# unified.net
KiCad netlist of a schematic drawn in EAGLE
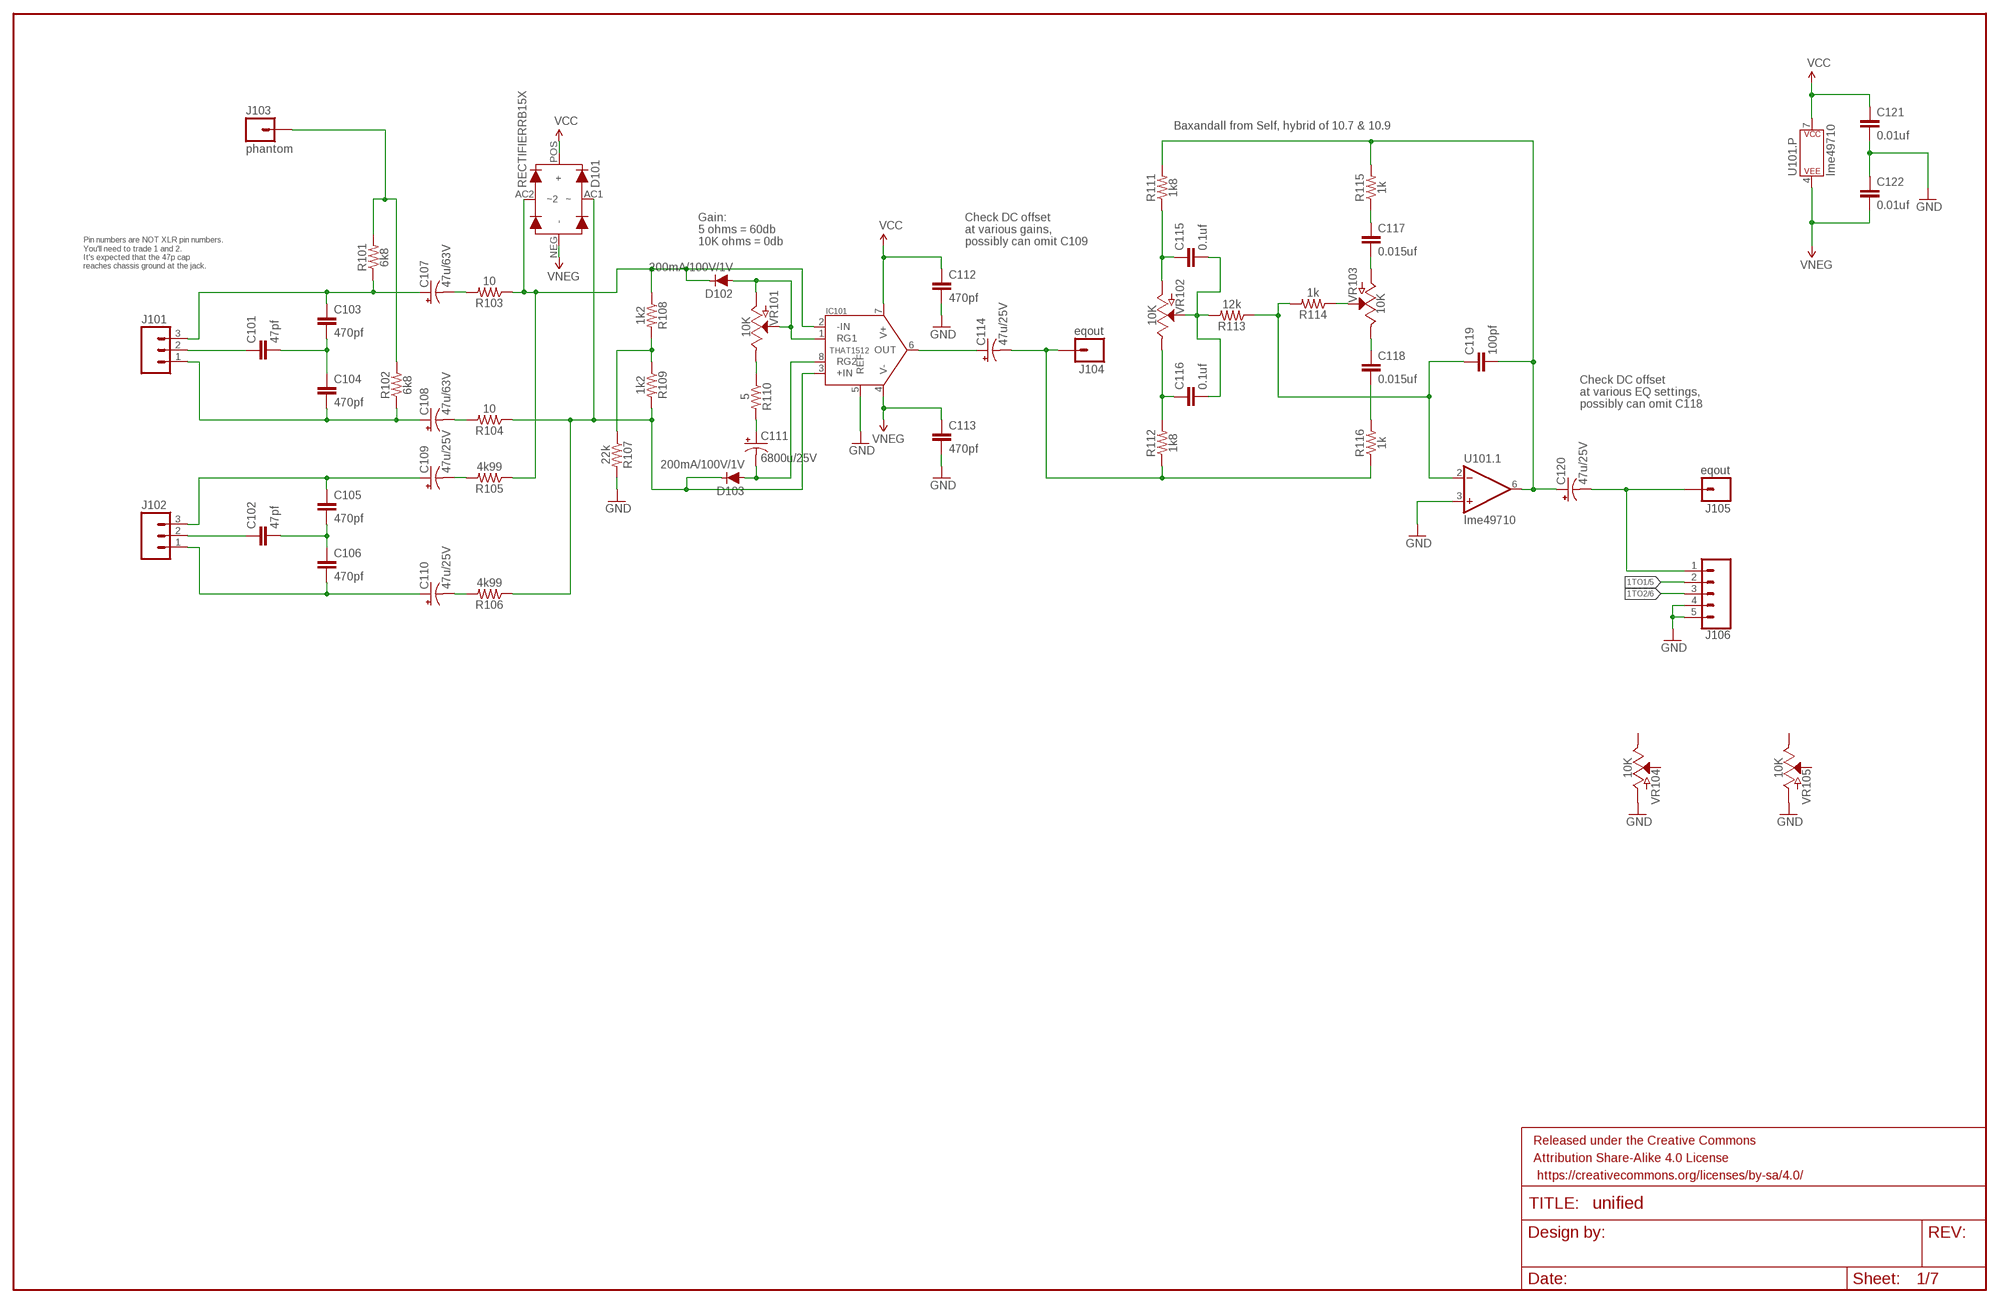
[diagram p0: schematic, sheet 1]
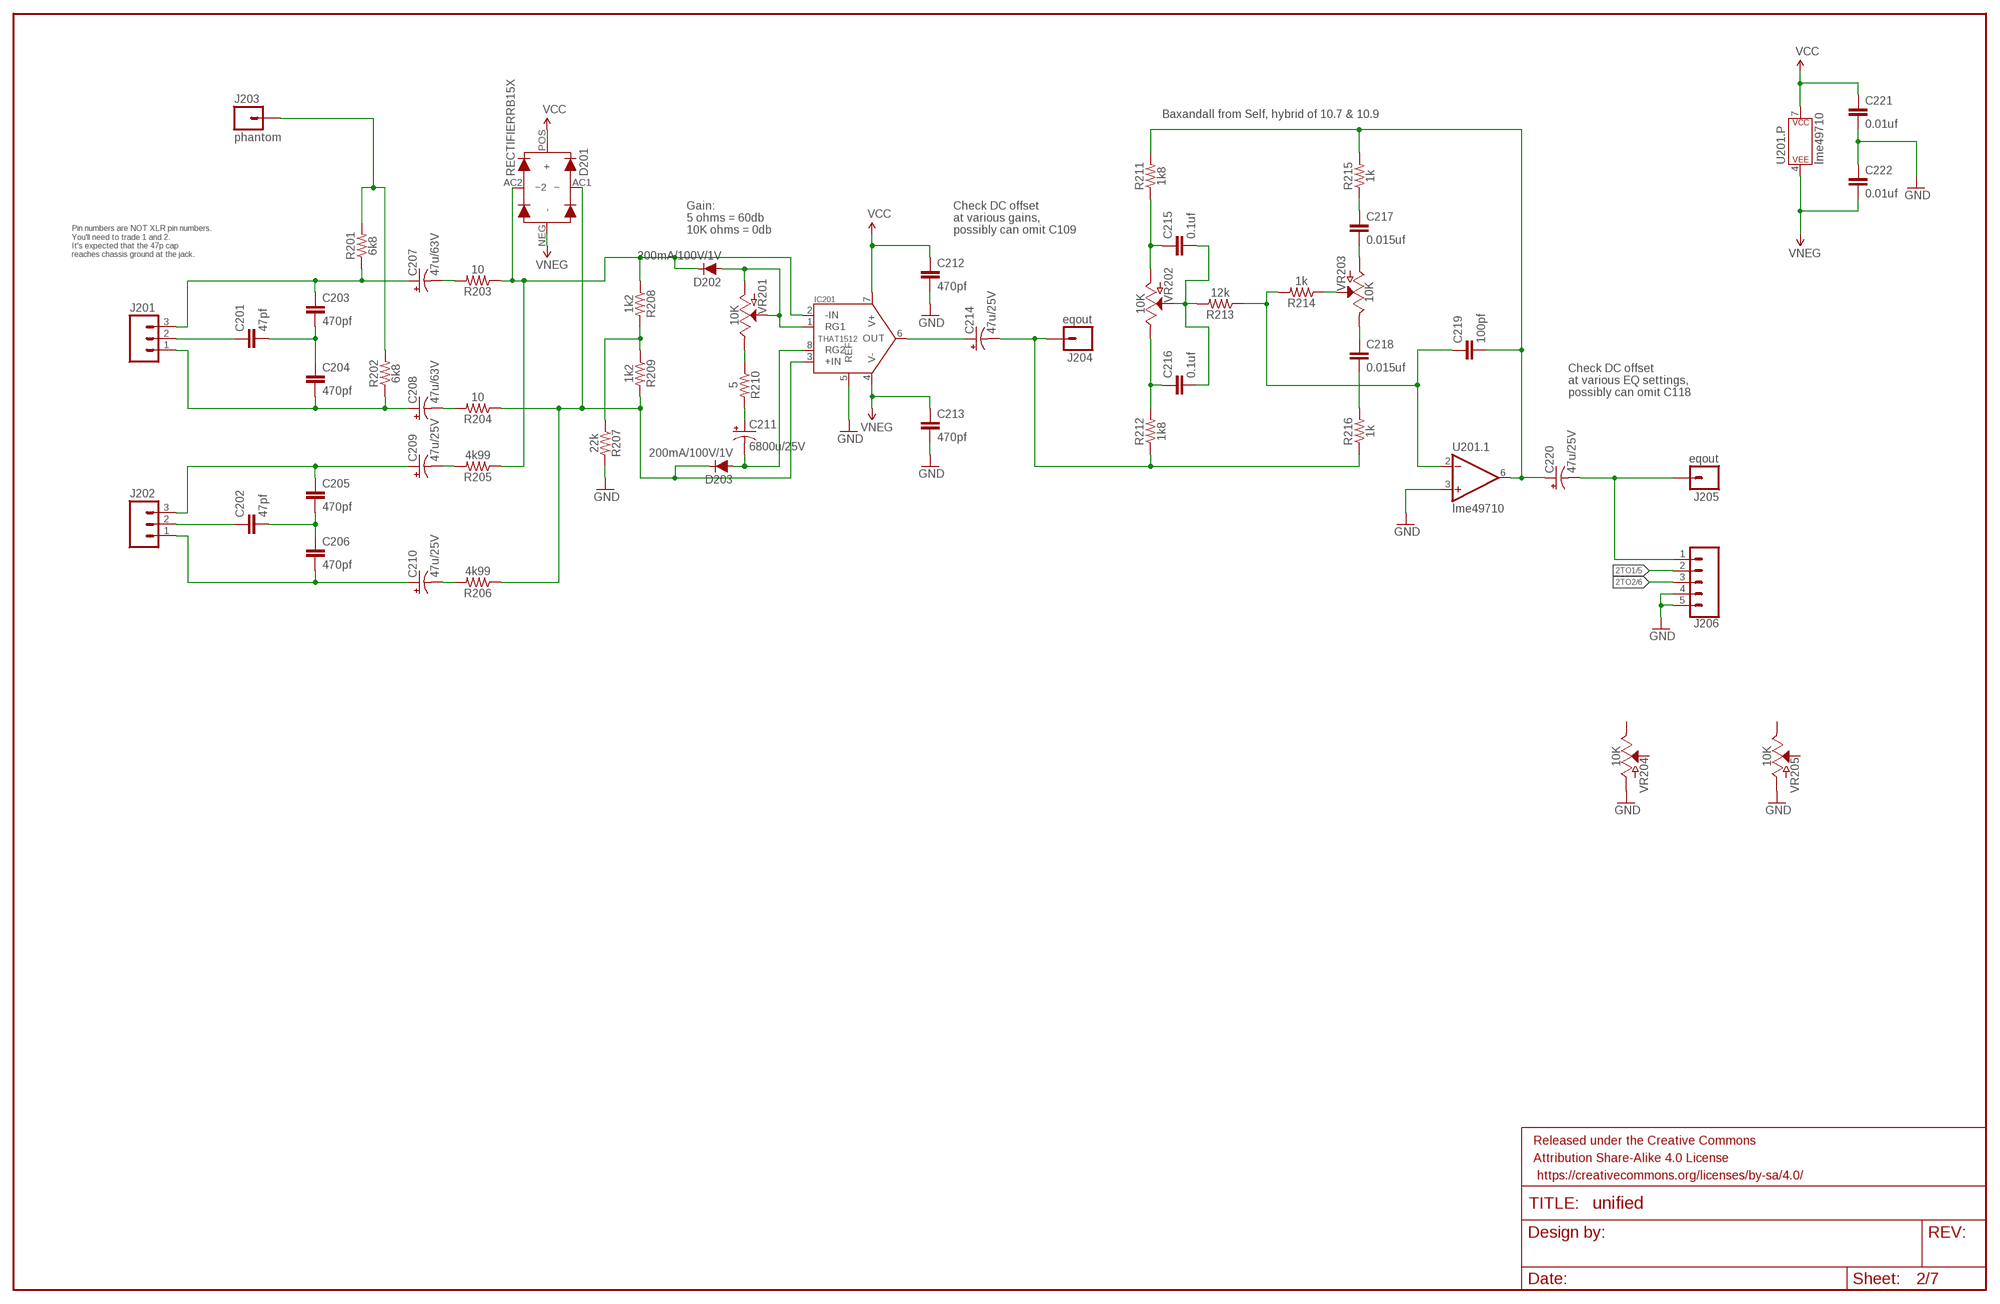
[diagram p1: schematic, sheet 2]
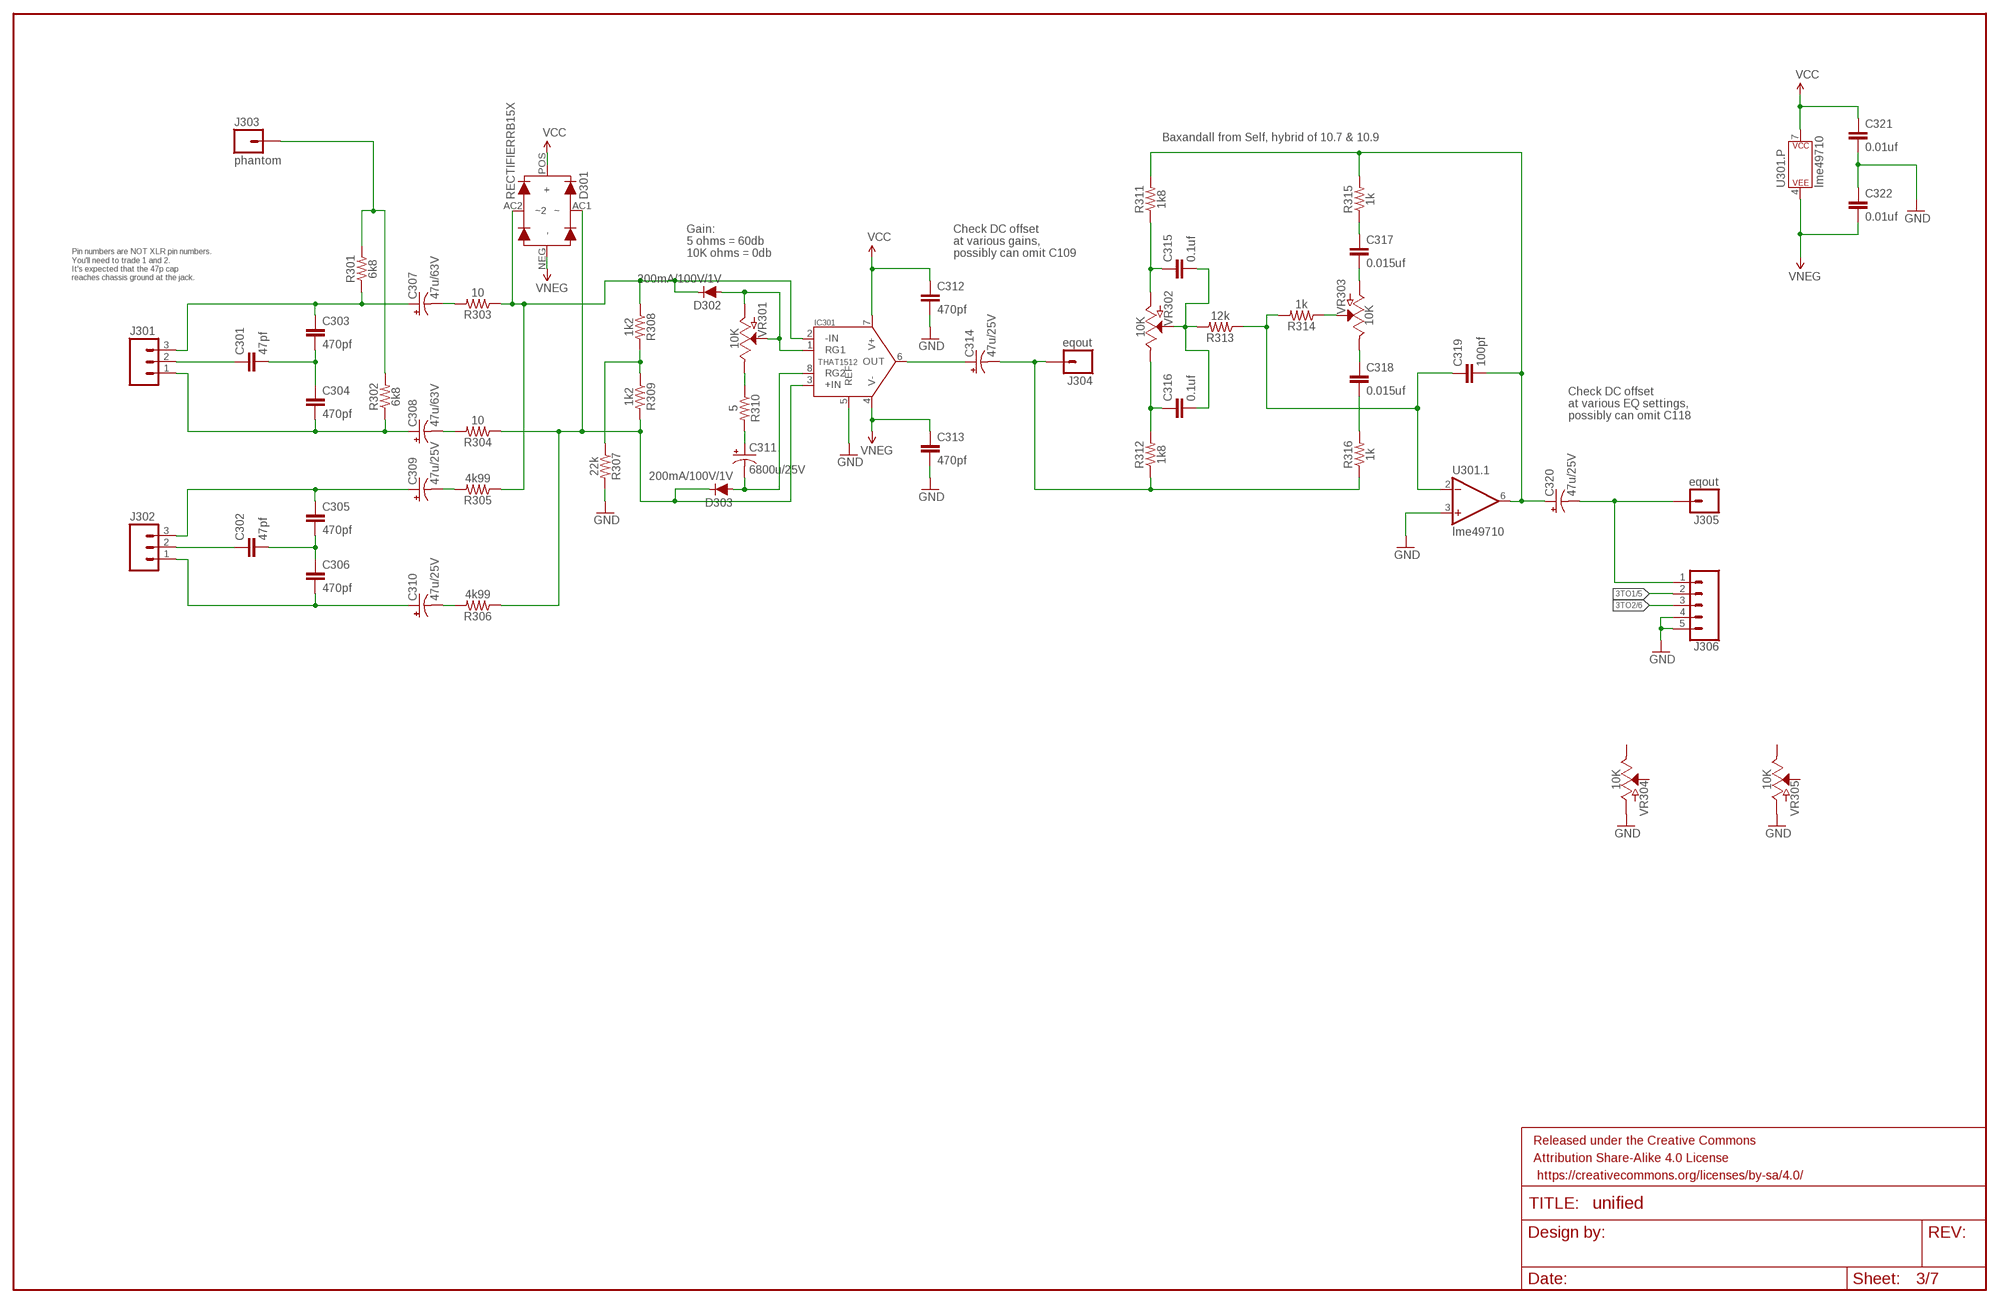
[diagram p2: schematic, sheet 3]
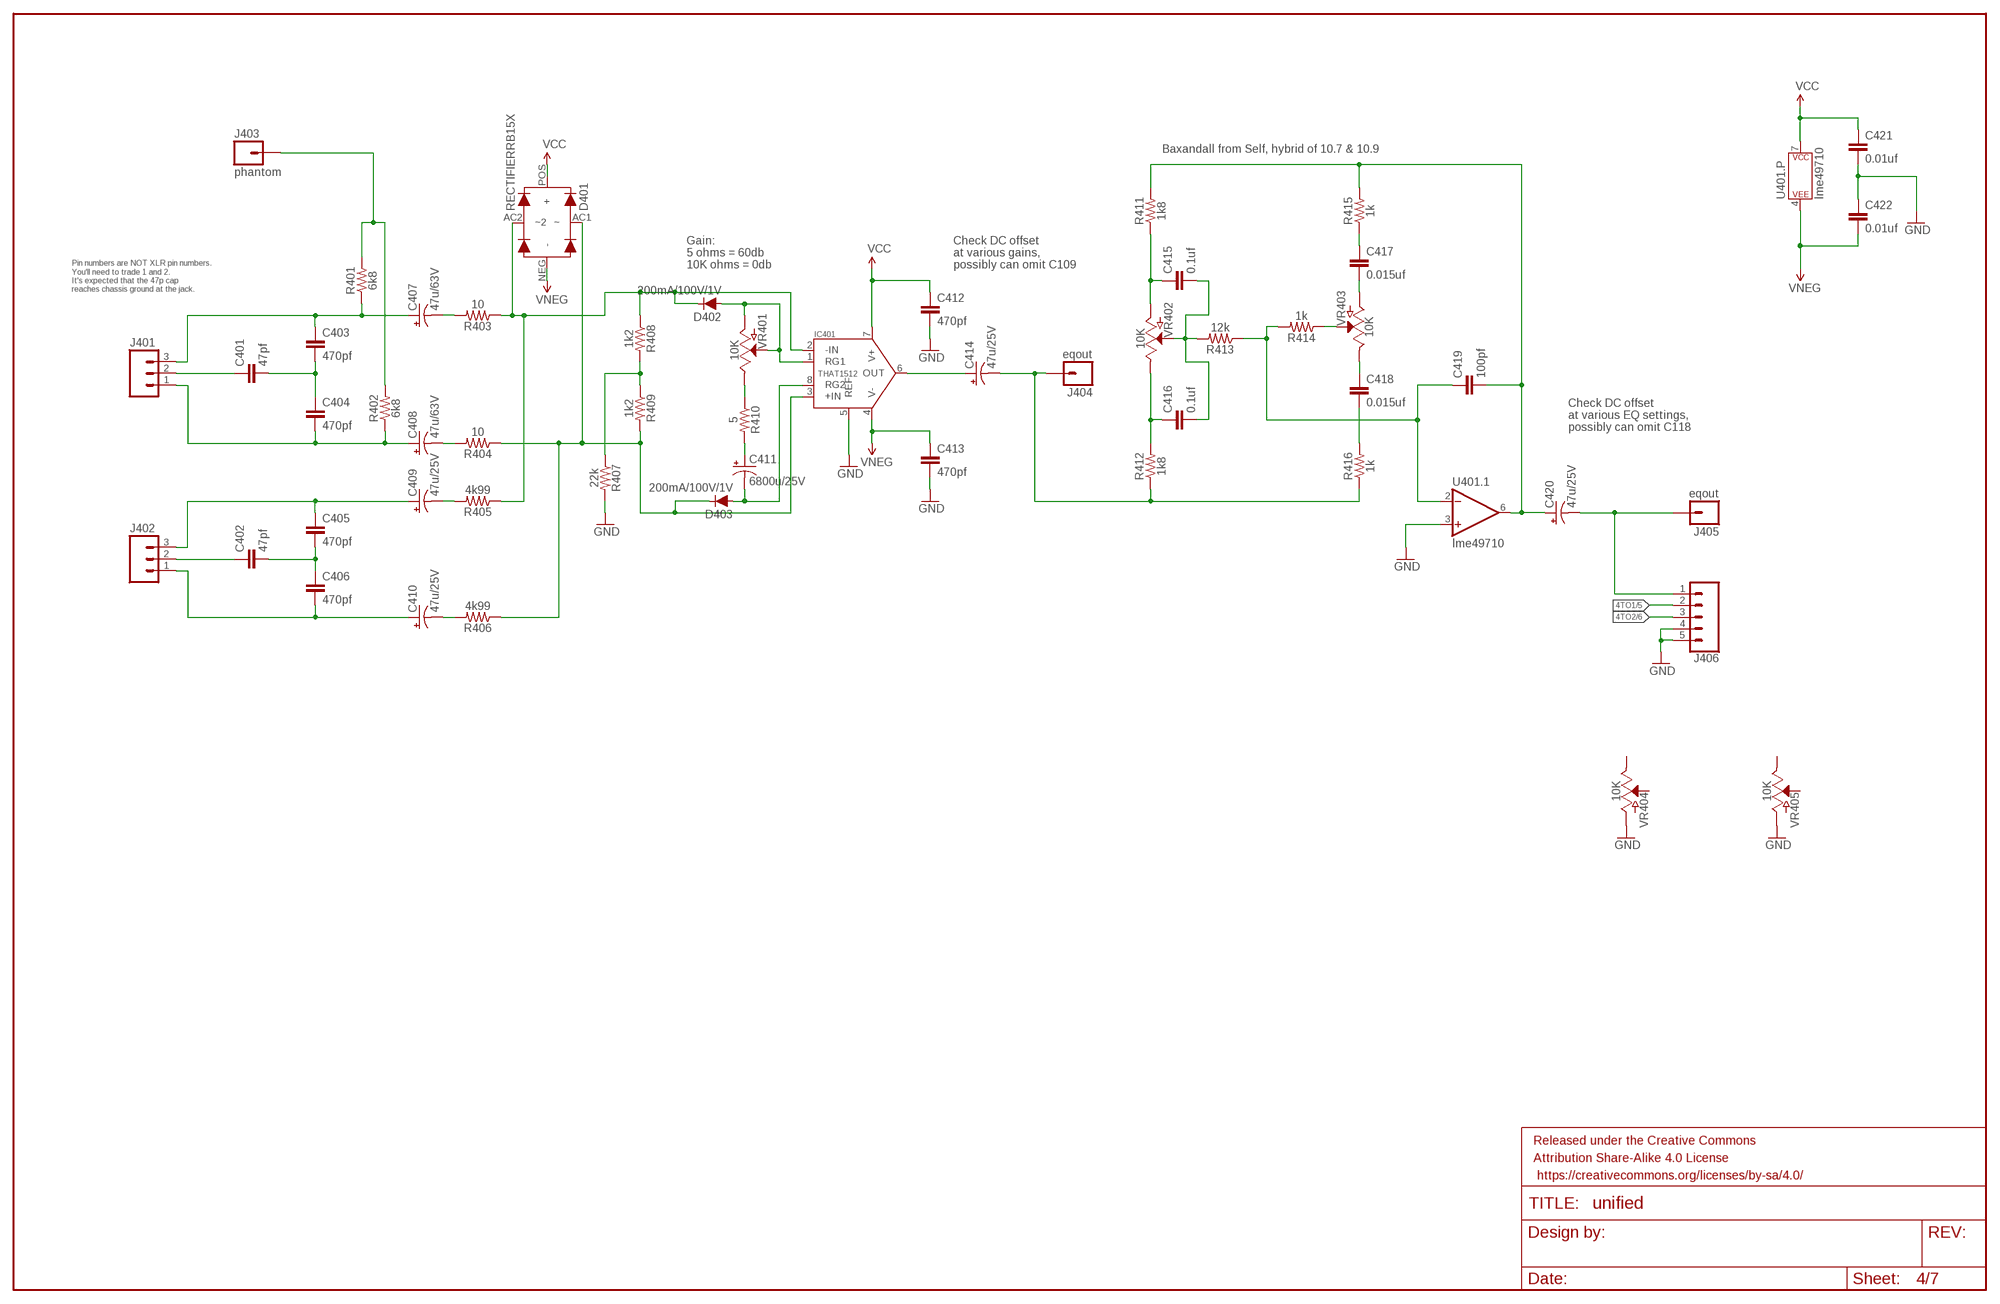
[diagram p3: schematic, sheet 4]
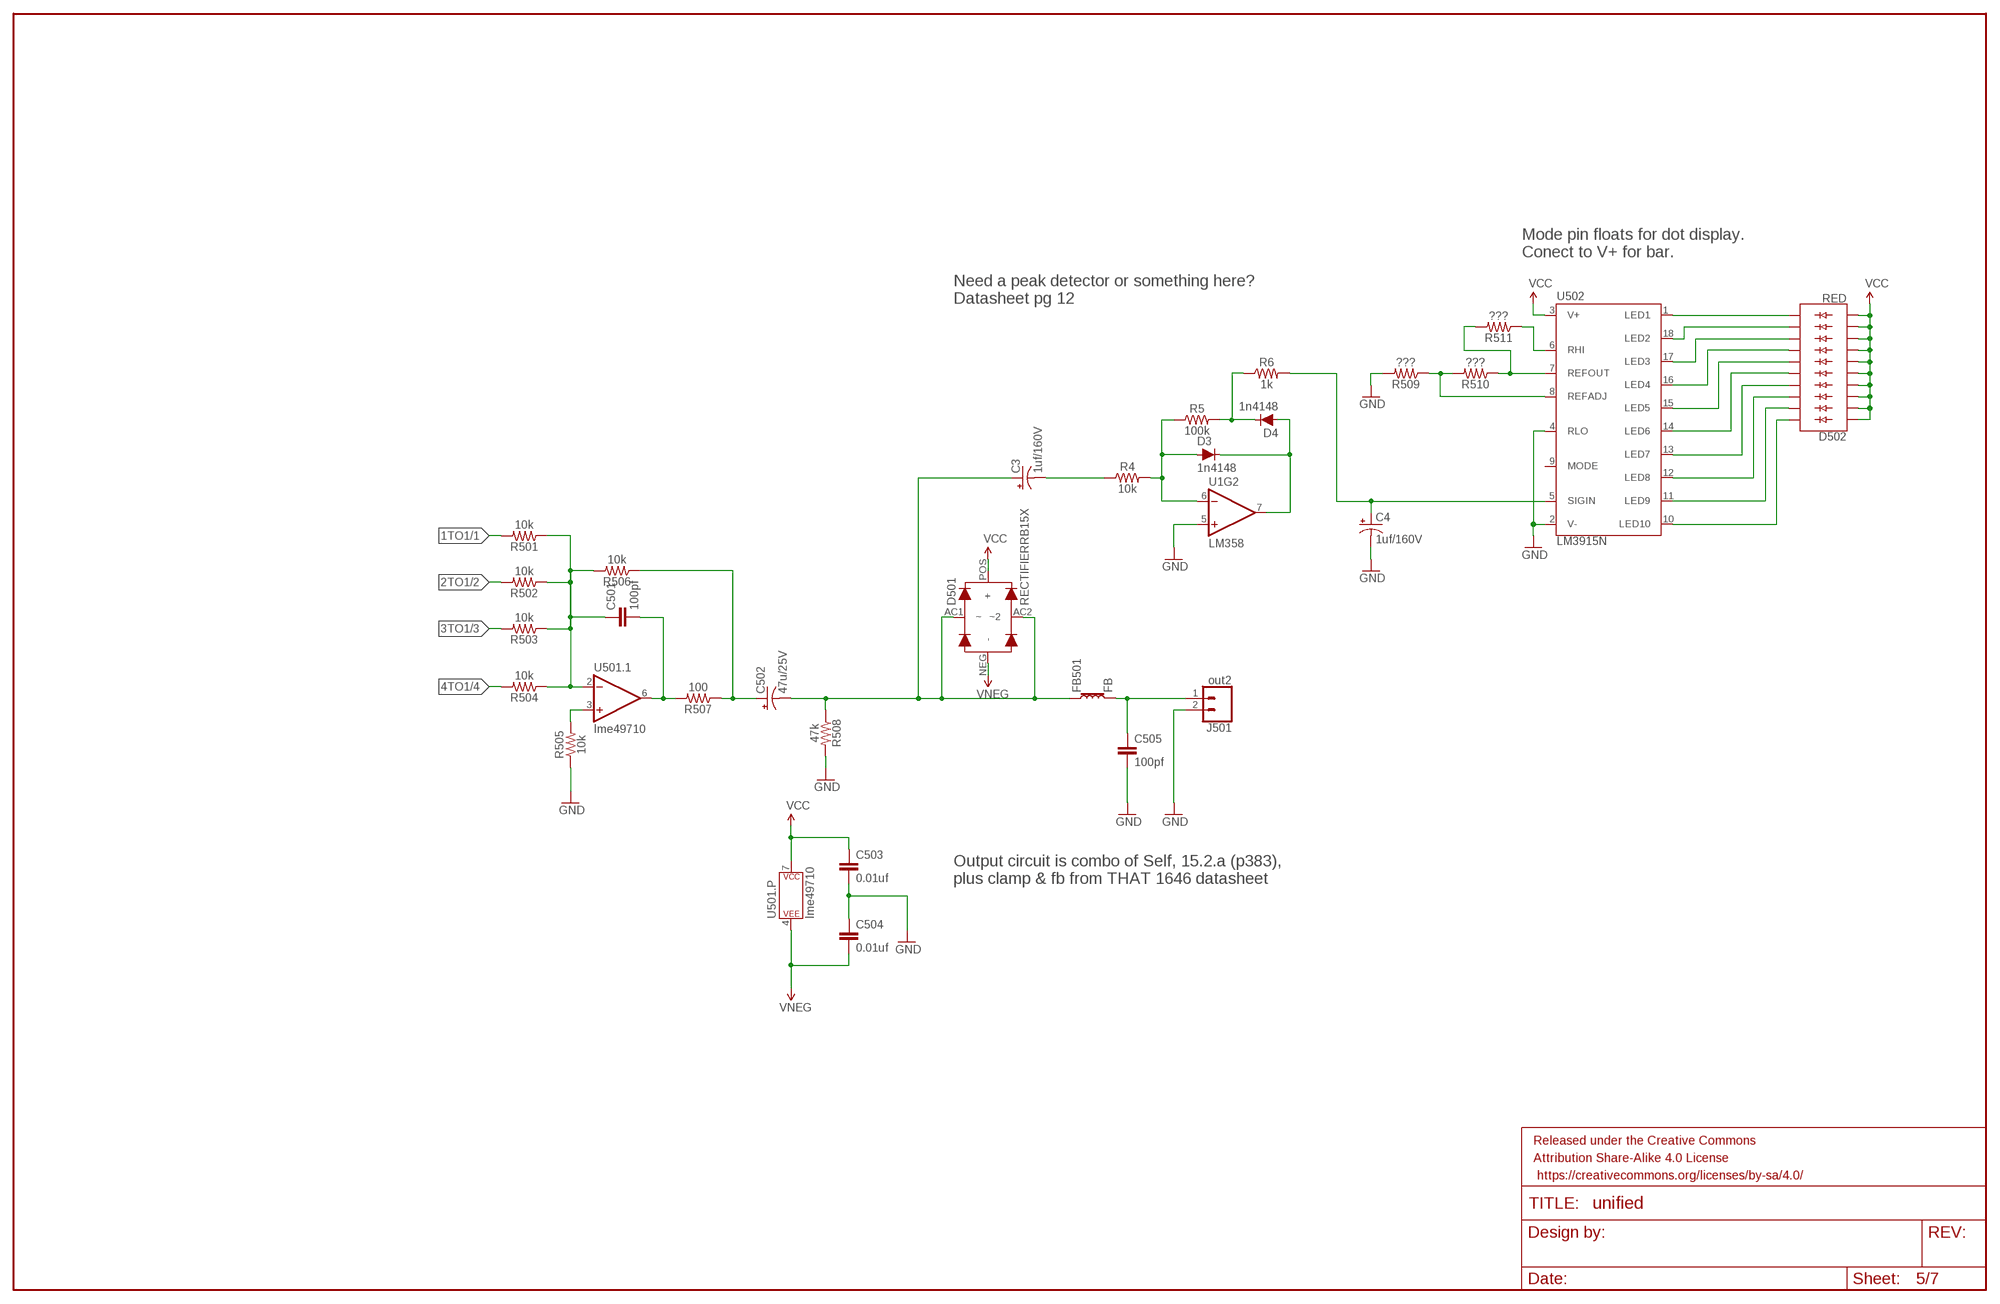
[diagram p4: schematic, sheet 5]
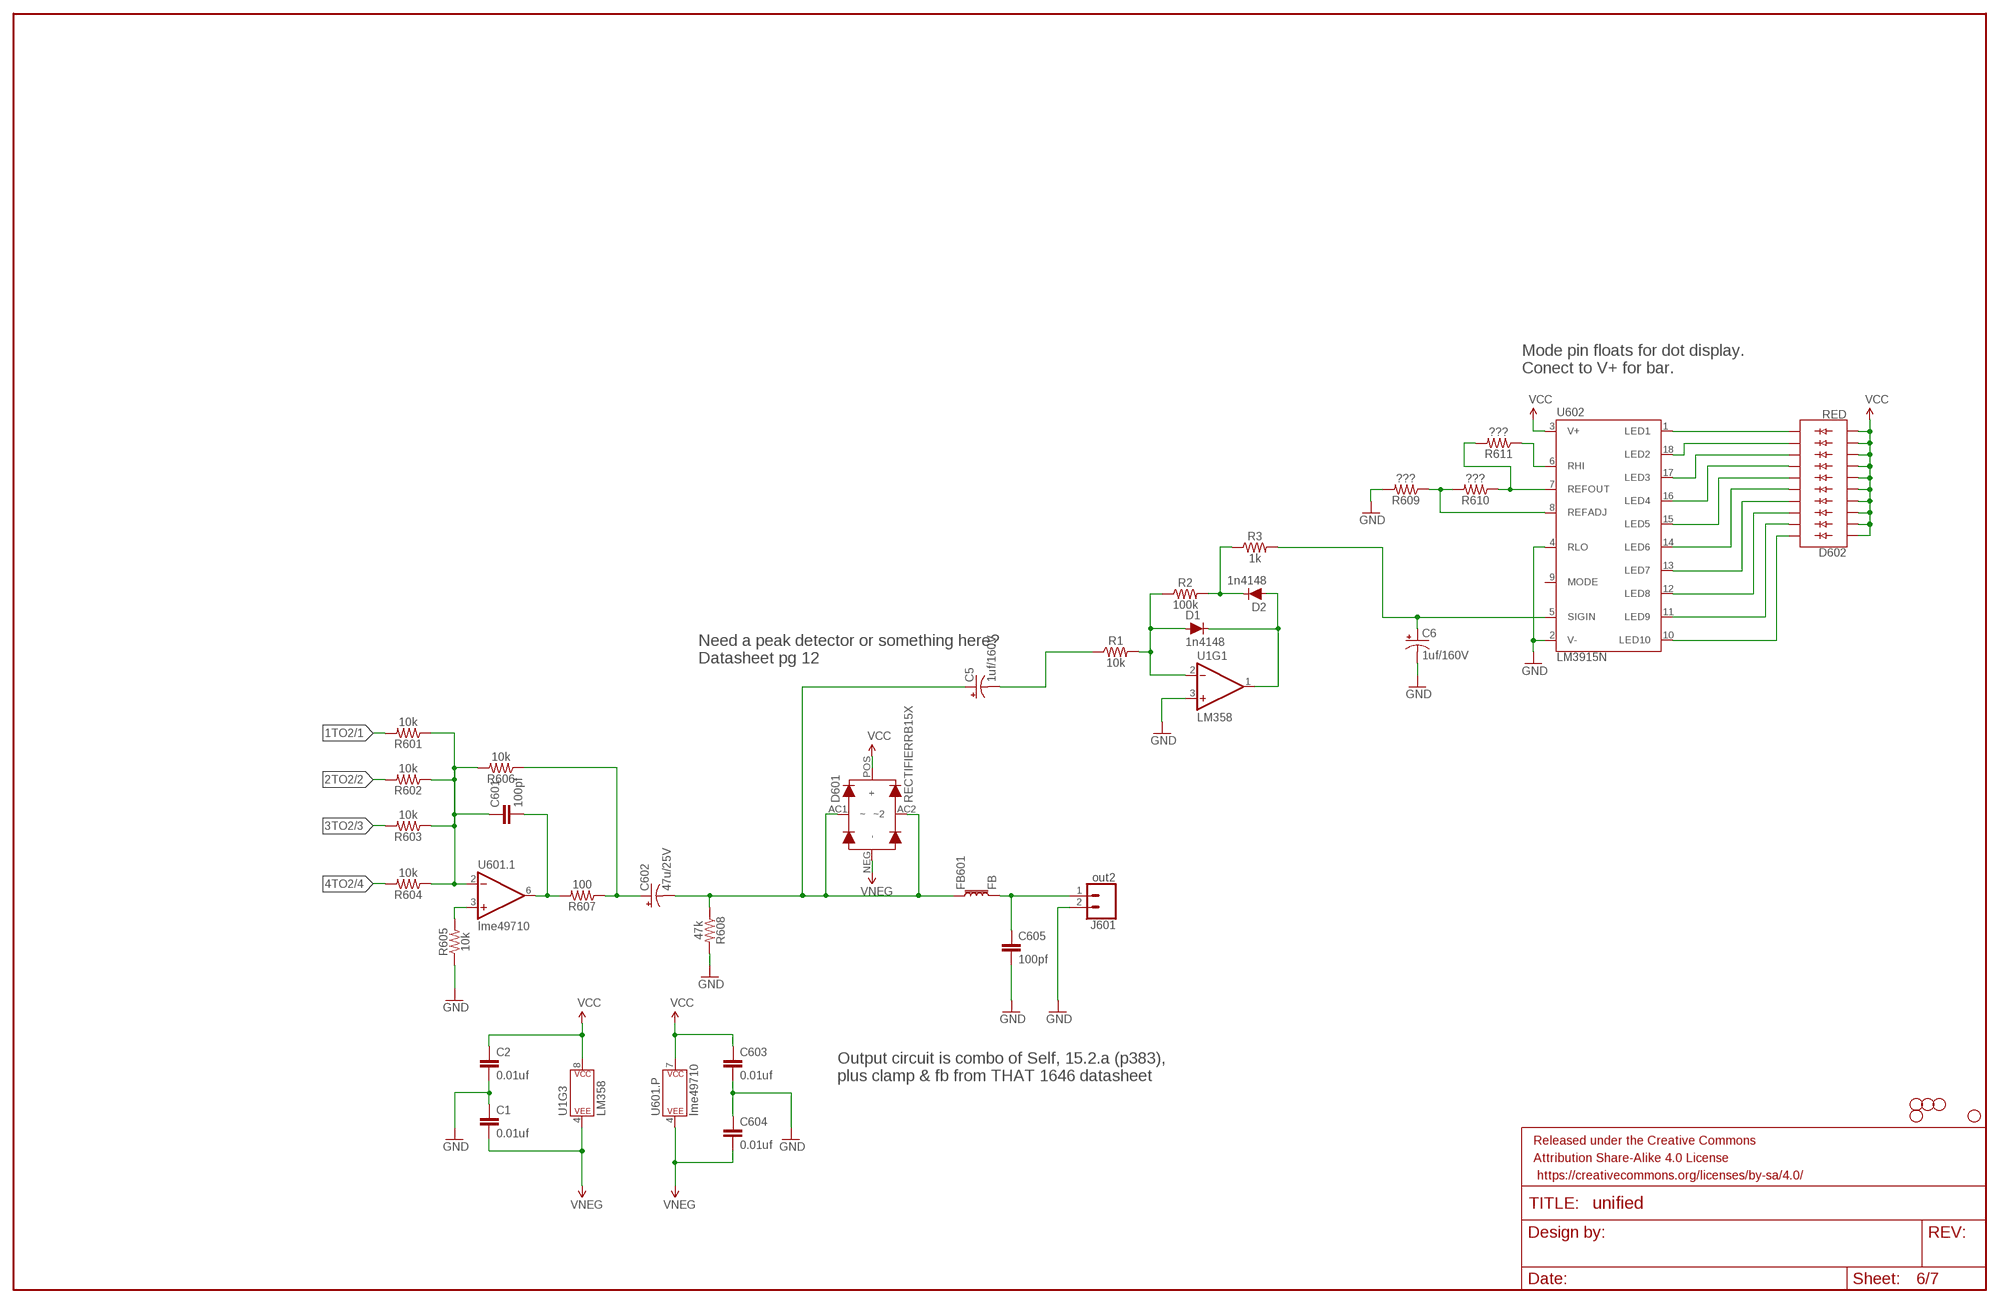
[diagram p5: schematic, sheet 6]
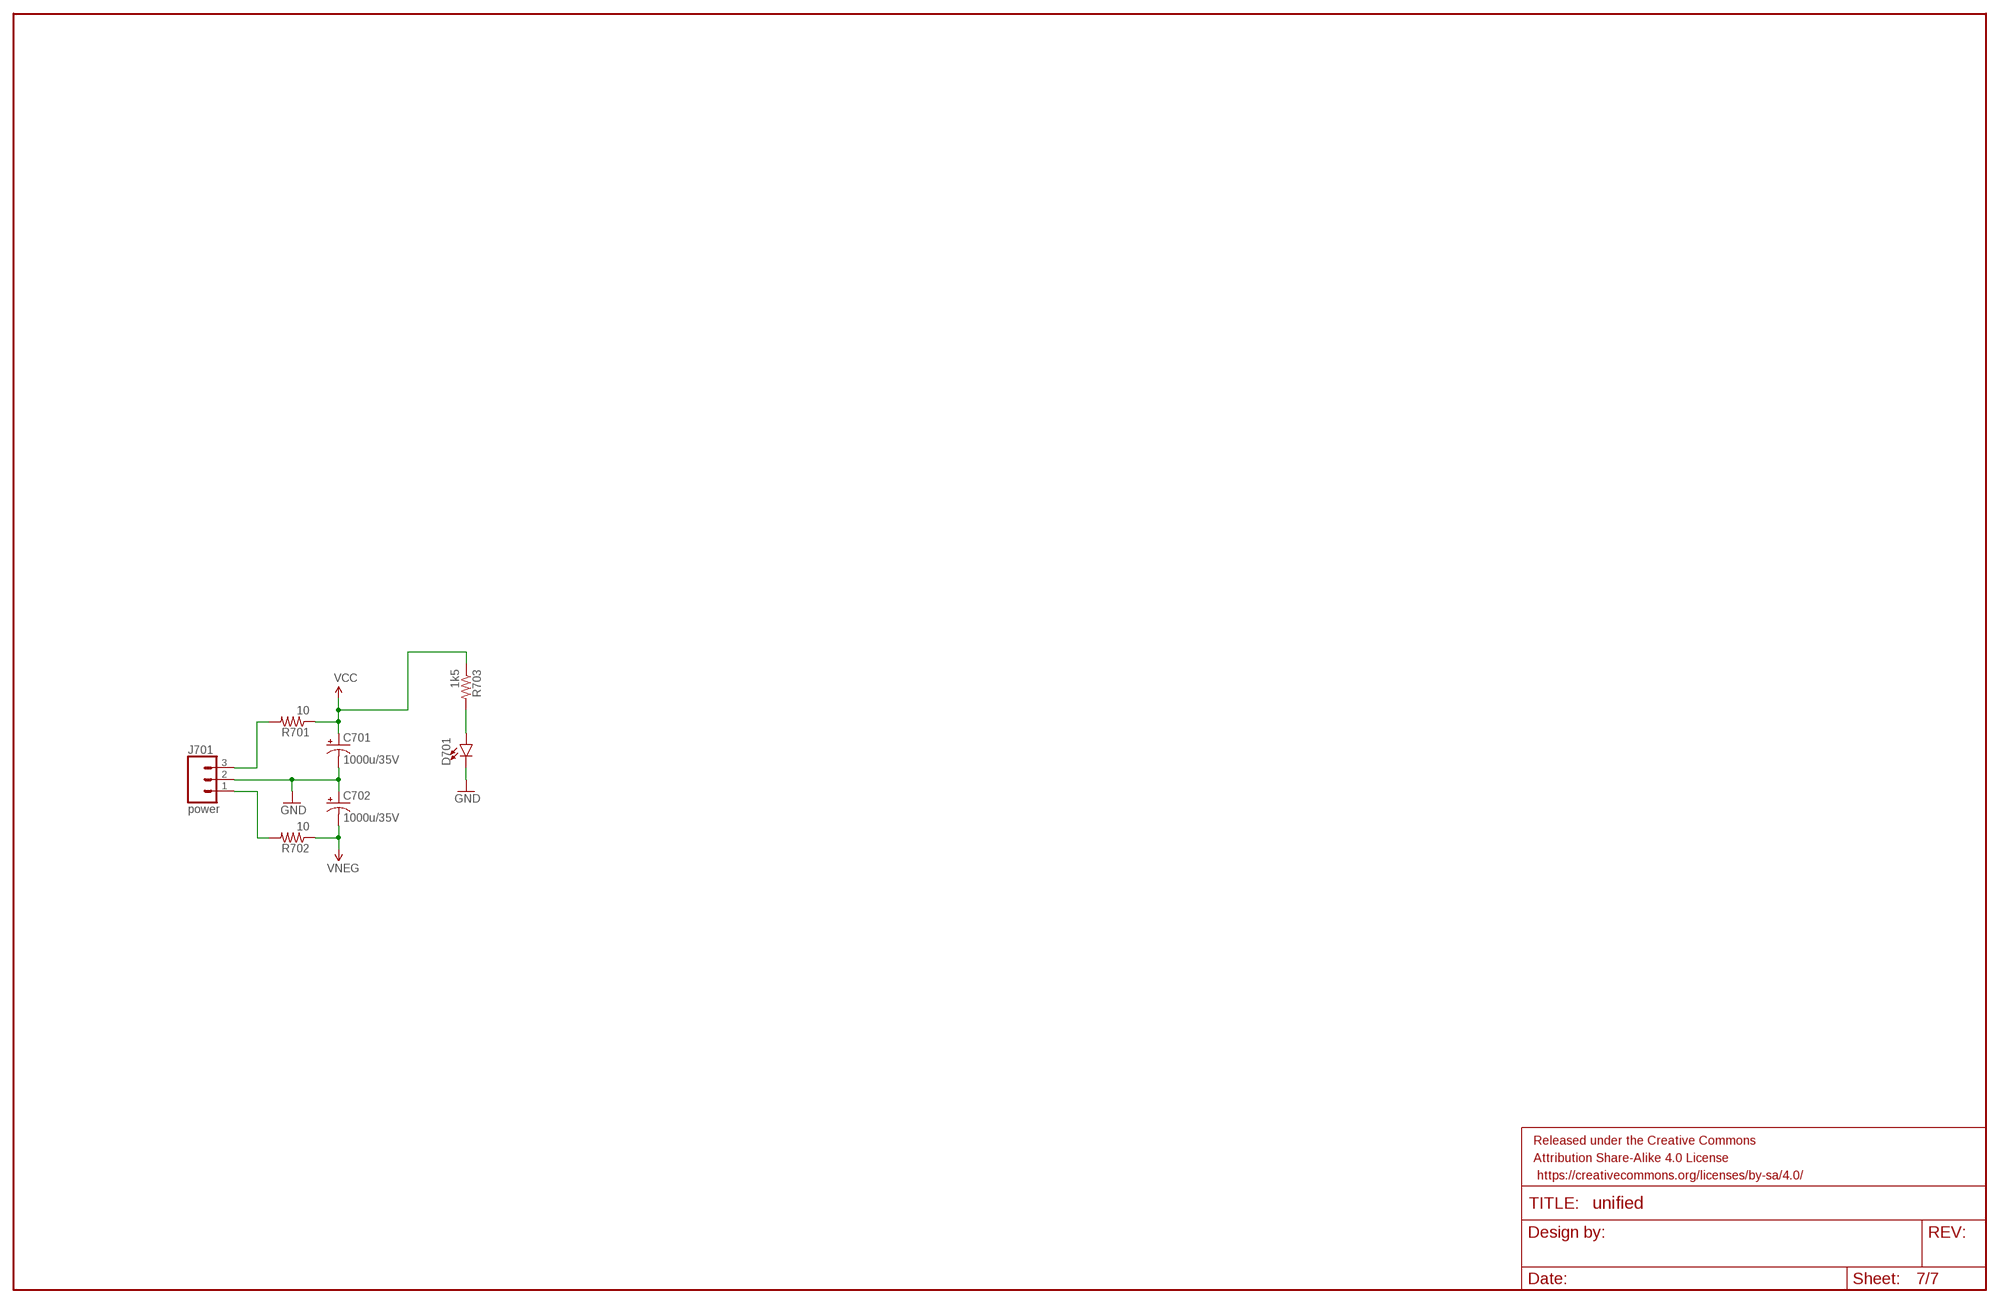
[diagram p6: schematic, sheet 7]

(export (version "E")
  (design (tool "Eeschema 10.0.6"))
  (components
    (comp (ref "C301")
      (value "47pf")
      (footprint "eagle-import:CAP-KEMET-GM-2.54LS")
      (libsource (lib "eagle-import") (part "CAP-CERAMIC47PF"))
    )
    (comp (ref "C302")
      (value "47pf")
      (footprint "eagle-import:CAP-KEMET-GM-2.54LS")
      (libsource (lib "eagle-import") (part "CAP-CERAMIC47PF"))
    )
    (comp (ref "C303")
      (value "470pf")
      (footprint "eagle-import:CAP-KEMET-GM-2.54LS")
      (libsource (lib "eagle-import") (part "CAP-CERAMIC470PF"))
    )
    (comp (ref "C304")
      (value "470pf")
      (footprint "eagle-import:CAP-KEMET-GM-2.54LS")
      (libsource (lib "eagle-import") (part "CAP-CERAMIC470PF"))
    )
    (comp (ref "C305")
      (value "470pf")
      (footprint "eagle-import:CAP-KEMET-GM-2.54LS")
      (libsource (lib "eagle-import") (part "CAP-CERAMIC470PF"))
    )
    (comp (ref "C306")
      (value "470pf")
      (footprint "eagle-import:CAP-KEMET-GM-2.54LS")
      (libsource (lib "eagle-import") (part "CAP-CERAMIC470PF"))
    )
    (comp (ref "C307")
      (value "47u/63V")
      (footprint "eagle-import:CAP-PANA-2LS-6DIAM")
      (libsource (lib "eagle-import") (part "CAP-LYTIC47U/63V"))
    )
    (comp (ref "C308")
      (value "47u/63V")
      (footprint "eagle-import:CAP-PANA-2LS-6DIAM")
      (libsource (lib "eagle-import") (part "CAP-LYTIC47U/63V"))
    )
    (comp (ref "C309")
      (value "47u/25V")
      (footprint "eagle-import:CAP-PANA-2LS-5DIAM")
      (libsource (lib "eagle-import") (part "CAP-LYTIC47U/25V"))
    )
    (comp (ref "C310")
      (value "47u/25V")
      (footprint "eagle-import:CAP-PANA-2LS-5DIAM")
      (libsource (lib "eagle-import") (part "CAP-LYTIC47U/25V"))
    )
    (comp (ref "C311")
      (value "6800u/25V")
      (footprint "eagle-import:CAP-PANA-5LS-12.5DIAM")
      (libsource (lib "eagle-import") (part "CAP-LYTIC6800U/10V"))
    )
    (comp (ref "C312")
      (value "470pf")
      (footprint "eagle-import:CAP-KEMET-GM-2.54LS")
      (libsource (lib "eagle-import") (part "CAP-CERAMIC470PF"))
    )
    (comp (ref "C313")
      (value "470pf")
      (footprint "eagle-import:CAP-KEMET-GM-2.54LS")
      (libsource (lib "eagle-import") (part "CAP-CERAMIC470PF"))
    )
    (comp (ref "C314")
      (value "47u/25V")
      (footprint "eagle-import:CAP-PANA-2LS-5DIAM")
      (libsource (lib "eagle-import") (part "CAP-LYTIC47U/25V"))
    )
    (comp (ref "C315")
      (value "0.1uf")
      (footprint "eagle-import:WIMA-MKS2-2.5X7.2")
      (libsource (lib "eagle-import") (part "WIMA-MKS20.1UF"))
    )
    (comp (ref "C316")
      (value "0.1uf")
      (footprint "eagle-import:WIMA-MKS2-2.5X7.2")
      (libsource (lib "eagle-import") (part "WIMA-MKS20.1UF"))
    )
    (comp (ref "C317")
      (value "0.015uf")
      (footprint "eagle-import:WIMA-MKS2-2.5X7.2")
      (libsource (lib "eagle-import") (part "WIMA-MKS20.015UF"))
    )
    (comp (ref "C318")
      (value "0.015uf")
      (footprint "eagle-import:WIMA-MKS2-2.5X7.2")
      (libsource (lib "eagle-import") (part "WIMA-MKS20.015UF"))
    )
    (comp (ref "C319")
      (value "100pf")
      (footprint "eagle-import:CAP-KEMET-GM-2.54LS")
      (libsource (lib "eagle-import") (part "CAP-CERAMIC100PF"))
    )
    (comp (ref "C320")
      (value "47u/25V")
      (footprint "eagle-import:CAP-PANA-2LS-5DIAM")
      (libsource (lib "eagle-import") (part "CAP-LYTIC47U/25V"))
    )
    (comp (ref "C321")
      (value "0.01uf")
      (footprint "eagle-import:WIMA-MKS2-2.5X7.2")
      (libsource (lib "eagle-import") (part "WIMA-MKS20.01UF"))
    )
    (comp (ref "C322")
      (value "0.01uf")
      (footprint "eagle-import:WIMA-MKS2-2.5X7.2")
      (libsource (lib "eagle-import") (part "WIMA-MKS20.01UF"))
    )
    (comp (ref "D301")
      (value "RECTIFIERRB15X")
      (footprint "eagle-import:SM-RECTIFIER")
      (libsource (lib "eagle-import") (part "RECTIFIERRB15X"))
    )
    (comp (ref "D302")
      (value "200mA/100V/1V")
      (footprint "eagle-import:DIODE-1N4148")
      (libsource (lib "eagle-import") (part "DIODE-1N4148"))
    )
    (comp (ref "D303")
      (value "200mA/100V/1V")
      (footprint "eagle-import:DIODE-1N4148")
      (libsource (lib "eagle-import") (part "DIODE-1N4148"))
    )
    (comp (ref "FRAME301")
      (value "FRAME-LEDGER")
      (footprint "eagle-import:CREATIVE_COMMONS")
      (libsource (lib "eagle-import") (part "FRAME-LEDGER"))
    )
    (comp (ref "IC301")
      (value "THAT1512")
      (footprint "eagle-import:DIP08-KIT")
      (libsource (lib "eagle-import") (part "THAT151X"))
    )
    (comp (ref "J301")
      (value "M031X03_NO_SILK")
      (footprint "eagle-import:1X03_NO_SILK@1")
      (libsource (lib "eagle-import") (part "M031X03_NO_SILK"))
    )
    (comp (ref "J302")
      (value "M031X03_NO_SILK")
      (footprint "eagle-import:1X03_NO_SILK@1")
      (libsource (lib "eagle-import") (part "M031X03_NO_SILK"))
    )
    (comp (ref "J303")
      (value "phantom")
      (footprint "eagle-import:1X01NS-KIT")
      (libsource (lib "eagle-import") (part "M01NOSILK-KIT"))
    )
    (comp (ref "J304")
      (value "eqout")
      (footprint "eagle-import:1X01NS-KIT")
      (libsource (lib "eagle-import") (part "M01NOSILK-KIT"))
    )
    (comp (ref "J305")
      (value "eqout")
      (footprint "eagle-import:1X01NS-KIT")
      (libsource (lib "eagle-import") (part "M01NOSILK-KIT"))
    )
    (comp (ref "J306")
      (value "CONN_05PTH_LONGPADS")
      (footprint "eagle-import:1X05_LONGPADS")
      (libsource (lib "eagle-import") (part "CONN_05PTH_LONGPADS"))
    )
    (comp (ref "R301")
      (value "6k8")
      (footprint "eagle-import:AXIAL-0.3")
      (libsource (lib "eagle-import") (part "RESISTOR"))
    )
    (comp (ref "R302")
      (value "6k8")
      (footprint "eagle-import:AXIAL-0.3")
      (libsource (lib "eagle-import") (part "RESISTOR"))
    )
    (comp (ref "R303")
      (value "10")
      (footprint "eagle-import:AXIAL-0.3")
      (libsource (lib "eagle-import") (part "RESISTOR"))
    )
    (comp (ref "R304")
      (value "10")
      (footprint "eagle-import:AXIAL-0.3")
      (libsource (lib "eagle-import") (part "RESISTOR"))
    )
    (comp (ref "R305")
      (value "4k99")
      (footprint "eagle-import:AXIAL-0.3")
      (libsource (lib "eagle-import") (part "RESISTOR"))
    )
    (comp (ref "R306")
      (value "4k99")
      (footprint "eagle-import:AXIAL-0.3")
      (libsource (lib "eagle-import") (part "RESISTOR"))
    )
    (comp (ref "R307")
      (value "22k")
      (footprint "eagle-import:AXIAL-0.3")
      (libsource (lib "eagle-import") (part "RESISTOR"))
    )
    (comp (ref "R308")
      (value "1k2")
      (footprint "eagle-import:AXIAL-0.3")
      (libsource (lib "eagle-import") (part "RESISTOR"))
    )
    (comp (ref "R309")
      (value "1k2")
      (footprint "eagle-import:AXIAL-0.3")
      (libsource (lib "eagle-import") (part "RESISTOR"))
    )
    (comp (ref "R310")
      (value "5")
      (footprint "eagle-import:AXIAL-0.3")
      (libsource (lib "eagle-import") (part "RESISTOR"))
    )
    (comp (ref "R311")
      (value "1k8")
      (footprint "eagle-import:AXIAL-0.3")
      (libsource (lib "eagle-import") (part "RESISTOR"))
    )
    (comp (ref "R312")
      (value "1k8")
      (footprint "eagle-import:AXIAL-0.3")
      (libsource (lib "eagle-import") (part "RESISTOR"))
    )
    (comp (ref "R313")
      (value "12k")
      (footprint "eagle-import:AXIAL-0.3")
      (libsource (lib "eagle-import") (part "RESISTOR"))
    )
    (comp (ref "R314")
      (value "1k")
      (footprint "eagle-import:AXIAL-0.3")
      (libsource (lib "eagle-import") (part "RESISTOR"))
    )
    (comp (ref "R315")
      (value "1k")
      (footprint "eagle-import:AXIAL-0.3")
      (libsource (lib "eagle-import") (part "RESISTOR"))
    )
    (comp (ref "R316")
      (value "1k")
      (footprint "eagle-import:AXIAL-0.3")
      (libsource (lib "eagle-import") (part "RESISTOR"))
    )
    (comp (ref "U301")
      (value "lme49710")
      (footprint "eagle-import:DIP08-KIT")
      (libsource (lib "eagle-import") (part "OPAMPLME49710"))
    )
    (comp (ref "VR301")
      (value "10K")
      (footprint "eagle-import:ROT-SW-POT")
      (libsource (lib "eagle-import") (part "POTROT-SW-POT"))
    )
    (comp (ref "VR302")
      (value "10K")
      (footprint "eagle-import:ALPHA-RV24AF40-POT")
      (libsource (lib "eagle-import") (part "POT10K-VERTPIN"))
    )
    (comp (ref "VR303")
      (value "10K")
      (footprint "eagle-import:ALPHA-RV24AF40-POT")
      (libsource (lib "eagle-import") (part "POT10K-VERTPIN"))
    )
    (comp (ref "VR304")
      (value "10K")
      (footprint "eagle-import:ALPHA-RV24AF40-POT")
      (libsource (lib "eagle-import") (part "POT10K-VERTPIN"))
    )
    (comp (ref "VR305")
      (value "10K")
      (footprint "eagle-import:ALPHA-RV24AF40-POT")
      (libsource (lib "eagle-import") (part "POT10K-VERTPIN"))
    )
    (comp (ref "C101")
      (value "47pf")
      (footprint "eagle-import:CAP-KEMET-GM-2.54LS")
      (libsource (lib "eagle-import") (part "CAP-CERAMIC47PF"))
    )
    (comp (ref "C102")
      (value "47pf")
      (footprint "eagle-import:CAP-KEMET-GM-2.54LS")
      (libsource (lib "eagle-import") (part "CAP-CERAMIC47PF"))
    )
    (comp (ref "C103")
      (value "470pf")
      (footprint "eagle-import:CAP-KEMET-GM-2.54LS")
      (libsource (lib "eagle-import") (part "CAP-CERAMIC470PF"))
    )
    (comp (ref "C104")
      (value "470pf")
      (footprint "eagle-import:CAP-KEMET-GM-2.54LS")
      (libsource (lib "eagle-import") (part "CAP-CERAMIC470PF"))
    )
    (comp (ref "C105")
      (value "470pf")
      (footprint "eagle-import:CAP-KEMET-GM-2.54LS")
      (libsource (lib "eagle-import") (part "CAP-CERAMIC470PF"))
    )
    (comp (ref "C106")
      (value "470pf")
      (footprint "eagle-import:CAP-KEMET-GM-2.54LS")
      (libsource (lib "eagle-import") (part "CAP-CERAMIC470PF"))
    )
    (comp (ref "C107")
      (value "47u/63V")
      (footprint "eagle-import:CAP-PANA-2LS-6DIAM")
      (libsource (lib "eagle-import") (part "CAP-LYTIC47U/63V"))
    )
    (comp (ref "C108")
      (value "47u/63V")
      (footprint "eagle-import:CAP-PANA-2LS-6DIAM")
      (libsource (lib "eagle-import") (part "CAP-LYTIC47U/63V"))
    )
    (comp (ref "C109")
      (value "47u/25V")
      (footprint "eagle-import:CAP-PANA-2LS-5DIAM")
      (libsource (lib "eagle-import") (part "CAP-LYTIC47U/25V"))
    )
    (comp (ref "C110")
      (value "47u/25V")
      (footprint "eagle-import:CAP-PANA-2LS-5DIAM")
      (libsource (lib "eagle-import") (part "CAP-LYTIC47U/25V"))
    )
    (comp (ref "C111")
      (value "6800u/25V")
      (footprint "eagle-import:CAP-PANA-5LS-12.5DIAM")
      (libsource (lib "eagle-import") (part "CAP-LYTIC6800U/10V"))
    )
    (comp (ref "C112")
      (value "470pf")
      (footprint "eagle-import:CAP-KEMET-GM-2.54LS")
      (libsource (lib "eagle-import") (part "CAP-CERAMIC470PF"))
    )
    (comp (ref "C113")
      (value "470pf")
      (footprint "eagle-import:CAP-KEMET-GM-2.54LS")
      (libsource (lib "eagle-import") (part "CAP-CERAMIC470PF"))
    )
    (comp (ref "C114")
      (value "47u/25V")
      (footprint "eagle-import:CAP-PANA-2LS-5DIAM")
      (libsource (lib "eagle-import") (part "CAP-LYTIC47U/25V"))
    )
    (comp (ref "C115")
      (value "0.1uf")
      (footprint "eagle-import:WIMA-MKS2-2.5X7.2")
      (libsource (lib "eagle-import") (part "WIMA-MKS20.1UF"))
    )
    (comp (ref "C116")
      (value "0.1uf")
      (footprint "eagle-import:WIMA-MKS2-2.5X7.2")
      (libsource (lib "eagle-import") (part "WIMA-MKS20.1UF"))
    )
    (comp (ref "C117")
      (value "0.015uf")
      (footprint "eagle-import:WIMA-MKS2-2.5X7.2")
      (libsource (lib "eagle-import") (part "WIMA-MKS20.015UF"))
    )
    (comp (ref "C118")
      (value "0.015uf")
      (footprint "eagle-import:WIMA-MKS2-2.5X7.2")
      (libsource (lib "eagle-import") (part "WIMA-MKS20.015UF"))
    )
    (comp (ref "C119")
      (value "100pf")
      (footprint "eagle-import:CAP-KEMET-GM-2.54LS")
      (libsource (lib "eagle-import") (part "CAP-CERAMIC100PF"))
    )
    (comp (ref "C120")
      (value "47u/25V")
      (footprint "eagle-import:CAP-PANA-2LS-5DIAM")
      (libsource (lib "eagle-import") (part "CAP-LYTIC47U/25V"))
    )
    (comp (ref "C121")
      (value "0.01uf")
      (footprint "eagle-import:WIMA-MKS2-2.5X7.2")
      (libsource (lib "eagle-import") (part "WIMA-MKS20.01UF"))
    )
    (comp (ref "C122")
      (value "0.01uf")
      (footprint "eagle-import:WIMA-MKS2-2.5X7.2")
      (libsource (lib "eagle-import") (part "WIMA-MKS20.01UF"))
    )
    (comp (ref "D101")
      (value "RECTIFIERRB15X")
      (footprint "eagle-import:SM-RECTIFIER")
      (libsource (lib "eagle-import") (part "RECTIFIERRB15X"))
    )
    (comp (ref "D102")
      (value "200mA/100V/1V")
      (footprint "eagle-import:DIODE-1N4148")
      (libsource (lib "eagle-import") (part "DIODE-1N4148"))
    )
    (comp (ref "D103")
      (value "200mA/100V/1V")
      (footprint "eagle-import:DIODE-1N4148")
      (libsource (lib "eagle-import") (part "DIODE-1N4148"))
    )
    (comp (ref "FRAME101")
      (value "FRAME-LEDGER")
      (footprint "eagle-import:CREATIVE_COMMONS")
      (libsource (lib "eagle-import") (part "FRAME-LEDGER"))
    )
    (comp (ref "IC101")
      (value "THAT1512")
      (footprint "eagle-import:DIP08-KIT")
      (libsource (lib "eagle-import") (part "THAT151X"))
    )
    (comp (ref "J101")
      (value "M031X03_NO_SILK")
      (footprint "eagle-import:1X03_NO_SILK@1")
      (libsource (lib "eagle-import") (part "M031X03_NO_SILK"))
    )
    (comp (ref "J102")
      (value "M031X03_NO_SILK")
      (footprint "eagle-import:1X03_NO_SILK@1")
      (libsource (lib "eagle-import") (part "M031X03_NO_SILK"))
    )
    (comp (ref "J103")
      (value "phantom")
      (footprint "eagle-import:1X01NS-KIT")
      (libsource (lib "eagle-import") (part "M01NOSILK-KIT"))
    )
    (comp (ref "J104")
      (value "eqout")
      (footprint "eagle-import:1X01NS-KIT")
      (libsource (lib "eagle-import") (part "M01NOSILK-KIT"))
    )
    (comp (ref "J105")
      (value "eqout")
      (footprint "eagle-import:1X01NS-KIT")
      (libsource (lib "eagle-import") (part "M01NOSILK-KIT"))
    )
    (comp (ref "J106")
      (value "CONN_05PTH_LONGPADS")
      (footprint "eagle-import:1X05_LONGPADS")
      (libsource (lib "eagle-import") (part "CONN_05PTH_LONGPADS"))
    )
    (comp (ref "R101")
      (value "6k8")
      (footprint "eagle-import:AXIAL-0.3")
      (libsource (lib "eagle-import") (part "RESISTOR"))
    )
    (comp (ref "R102")
      (value "6k8")
      (footprint "eagle-import:AXIAL-0.3")
      (libsource (lib "eagle-import") (part "RESISTOR"))
    )
    (comp (ref "R103")
      (value "10")
      (footprint "eagle-import:AXIAL-0.3")
      (libsource (lib "eagle-import") (part "RESISTOR"))
    )
    (comp (ref "R104")
      (value "10")
      (footprint "eagle-import:AXIAL-0.3")
      (libsource (lib "eagle-import") (part "RESISTOR"))
    )
    (comp (ref "R105")
      (value "4k99")
      (footprint "eagle-import:AXIAL-0.3")
      (libsource (lib "eagle-import") (part "RESISTOR"))
    )
    (comp (ref "R106")
      (value "4k99")
      (footprint "eagle-import:AXIAL-0.3")
      (libsource (lib "eagle-import") (part "RESISTOR"))
    )
    (comp (ref "R107")
      (value "22k")
      (footprint "eagle-import:AXIAL-0.3")
      (libsource (lib "eagle-import") (part "RESISTOR"))
    )
    (comp (ref "R108")
      (value "1k2")
      (footprint "eagle-import:AXIAL-0.3")
      (libsource (lib "eagle-import") (part "RESISTOR"))
    )
    (comp (ref "R109")
      (value "1k2")
      (footprint "eagle-import:AXIAL-0.3")
      (libsource (lib "eagle-import") (part "RESISTOR"))
    )
    (comp (ref "R110")
      (value "5")
      (footprint "eagle-import:AXIAL-0.3")
      (libsource (lib "eagle-import") (part "RESISTOR"))
    )
    (comp (ref "R111")
      (value "1k8")
      (footprint "eagle-import:AXIAL-0.3")
      (libsource (lib "eagle-import") (part "RESISTOR"))
    )
    (comp (ref "R112")
      (value "1k8")
      (footprint "eagle-import:AXIAL-0.3")
      (libsource (lib "eagle-import") (part "RESISTOR"))
    )
    (comp (ref "R113")
      (value "12k")
      (footprint "eagle-import:AXIAL-0.3")
      (libsource (lib "eagle-import") (part "RESISTOR"))
    )
    (comp (ref "R114")
      (value "1k")
      (footprint "eagle-import:AXIAL-0.3")
      (libsource (lib "eagle-import") (part "RESISTOR"))
    )
    (comp (ref "R115")
      (value "1k")
      (footprint "eagle-import:AXIAL-0.3")
      (libsource (lib "eagle-import") (part "RESISTOR"))
    )
    (comp (ref "R116")
      (value "1k")
      (footprint "eagle-import:AXIAL-0.3")
      (libsource (lib "eagle-import") (part "RESISTOR"))
    )
    (comp (ref "U101")
      (value "lme49710")
      (footprint "eagle-import:DIP08-KIT")
      (libsource (lib "eagle-import") (part "OPAMPLME49710"))
    )
    (comp (ref "VR101")
      (value "10K")
      (footprint "eagle-import:ROT-SW-POT")
      (libsource (lib "eagle-import") (part "POTROT-SW-POT"))
    )
    (comp (ref "VR102")
      (value "10K")
      (footprint "eagle-import:ALPHA-RV24AF40-POT")
      (libsource (lib "eagle-import") (part "POT10K-VERTPIN"))
    )
    (comp (ref "VR103")
      (value "10K")
      (footprint "eagle-import:ALPHA-RV24AF40-POT")
      (libsource (lib "eagle-import") (part "POT10K-VERTPIN"))
    )
    (comp (ref "VR104")
      (value "10K")
      (footprint "eagle-import:ALPHA-RV24AF40-POT")
      (libsource (lib "eagle-import") (part "POT10K-VERTPIN"))
    )
    (comp (ref "VR105")
      (value "10K")
      (footprint "eagle-import:ALPHA-RV24AF40-POT")
      (libsource (lib "eagle-import") (part "POT10K-VERTPIN"))
    )
    (comp (ref "C201")
      (value "47pf")
      (footprint "eagle-import:CAP-KEMET-GM-2.54LS")
      (libsource (lib "eagle-import") (part "CAP-CERAMIC47PF"))
    )
    (comp (ref "C202")
      (value "47pf")
      (footprint "eagle-import:CAP-KEMET-GM-2.54LS")
      (libsource (lib "eagle-import") (part "CAP-CERAMIC47PF"))
    )
    (comp (ref "C203")
      (value "470pf")
      (footprint "eagle-import:CAP-KEMET-GM-2.54LS")
      (libsource (lib "eagle-import") (part "CAP-CERAMIC470PF"))
    )
    (comp (ref "C204")
      (value "470pf")
      (footprint "eagle-import:CAP-KEMET-GM-2.54LS")
      (libsource (lib "eagle-import") (part "CAP-CERAMIC470PF"))
    )
    (comp (ref "C205")
      (value "470pf")
      (footprint "eagle-import:CAP-KEMET-GM-2.54LS")
      (libsource (lib "eagle-import") (part "CAP-CERAMIC470PF"))
    )
    (comp (ref "C206")
      (value "470pf")
      (footprint "eagle-import:CAP-KEMET-GM-2.54LS")
      (libsource (lib "eagle-import") (part "CAP-CERAMIC470PF"))
    )
    (comp (ref "C207")
      (value "47u/63V")
      (footprint "eagle-import:CAP-PANA-2LS-6DIAM")
      (libsource (lib "eagle-import") (part "CAP-LYTIC47U/63V"))
    )
    (comp (ref "C208")
      (value "47u/63V")
      (footprint "eagle-import:CAP-PANA-2LS-6DIAM")
      (libsource (lib "eagle-import") (part "CAP-LYTIC47U/63V"))
    )
    (comp (ref "C209")
      (value "47u/25V")
      (footprint "eagle-import:CAP-PANA-2LS-5DIAM")
      (libsource (lib "eagle-import") (part "CAP-LYTIC47U/25V"))
    )
    (comp (ref "C210")
      (value "47u/25V")
      (footprint "eagle-import:CAP-PANA-2LS-5DIAM")
      (libsource (lib "eagle-import") (part "CAP-LYTIC47U/25V"))
    )
    (comp (ref "C211")
      (value "6800u/25V")
      (footprint "eagle-import:CAP-PANA-5LS-12.5DIAM")
      (libsource (lib "eagle-import") (part "CAP-LYTIC6800U/10V"))
    )
    (comp (ref "C212")
      (value "470pf")
      (footprint "eagle-import:CAP-KEMET-GM-2.54LS")
      (libsource (lib "eagle-import") (part "CAP-CERAMIC470PF"))
    )
    (comp (ref "C213")
      (value "470pf")
      (footprint "eagle-import:CAP-KEMET-GM-2.54LS")
      (libsource (lib "eagle-import") (part "CAP-CERAMIC470PF"))
    )
    (comp (ref "C214")
      (value "47u/25V")
      (footprint "eagle-import:CAP-PANA-2LS-5DIAM")
      (libsource (lib "eagle-import") (part "CAP-LYTIC47U/25V"))
    )
    (comp (ref "C215")
      (value "0.1uf")
      (footprint "eagle-import:WIMA-MKS2-2.5X7.2")
      (libsource (lib "eagle-import") (part "WIMA-MKS20.1UF"))
    )
    (comp (ref "C216")
      (value "0.1uf")
      (footprint "eagle-import:WIMA-MKS2-2.5X7.2")
      (libsource (lib "eagle-import") (part "WIMA-MKS20.1UF"))
    )
    (comp (ref "C217")
      (value "0.015uf")
      (footprint "eagle-import:WIMA-MKS2-2.5X7.2")
      (libsource (lib "eagle-import") (part "WIMA-MKS20.015UF"))
    )
    (comp (ref "C218")
      (value "0.015uf")
      (footprint "eagle-import:WIMA-MKS2-2.5X7.2")
      (libsource (lib "eagle-import") (part "WIMA-MKS20.015UF"))
    )
    (comp (ref "C219")
      (value "100pf")
      (footprint "eagle-import:CAP-KEMET-GM-2.54LS")
      (libsource (lib "eagle-import") (part "CAP-CERAMIC100PF"))
    )
    (comp (ref "C220")
      (value "47u/25V")
      (footprint "eagle-import:CAP-PANA-2LS-5DIAM")
      (libsource (lib "eagle-import") (part "CAP-LYTIC47U/25V"))
    )
    (comp (ref "C221")
      (value "0.01uf")
      (footprint "eagle-import:WIMA-MKS2-2.5X7.2")
      (libsource (lib "eagle-import") (part "WIMA-MKS20.01UF"))
    )
    (comp (ref "C222")
      (value "0.01uf")
      (footprint "eagle-import:WIMA-MKS2-2.5X7.2")
      (libsource (lib "eagle-import") (part "WIMA-MKS20.01UF"))
    )
    (comp (ref "D201")
      (value "RECTIFIERRB15X")
      (footprint "eagle-import:SM-RECTIFIER")
      (libsource (lib "eagle-import") (part "RECTIFIERRB15X"))
    )
    (comp (ref "D202")
      (value "200mA/100V/1V")
      (footprint "eagle-import:DIODE-1N4148")
      (libsource (lib "eagle-import") (part "DIODE-1N4148"))
    )
    (comp (ref "D203")
      (value "200mA/100V/1V")
      (footprint "eagle-import:DIODE-1N4148")
      (libsource (lib "eagle-import") (part "DIODE-1N4148"))
    )
    (comp (ref "FRAME201")
      (value "FRAME-LEDGER")
      (footprint "eagle-import:CREATIVE_COMMONS")
      (libsource (lib "eagle-import") (part "FRAME-LEDGER"))
    )
    (comp (ref "IC201")
      (value "THAT1512")
      (footprint "eagle-import:DIP08-KIT")
      (libsource (lib "eagle-import") (part "THAT151X"))
    )
    (comp (ref "J201")
      (value "M031X03_NO_SILK")
      (footprint "eagle-import:1X03_NO_SILK@1")
      (libsource (lib "eagle-import") (part "M031X03_NO_SILK"))
    )
    (comp (ref "J202")
      (value "M031X03_NO_SILK")
      (footprint "eagle-import:1X03_NO_SILK@1")
      (libsource (lib "eagle-import") (part "M031X03_NO_SILK"))
    )
    (comp (ref "J203")
      (value "phantom")
      (footprint "eagle-import:1X01NS-KIT")
      (libsource (lib "eagle-import") (part "M01NOSILK-KIT"))
    )
    (comp (ref "J204")
      (value "eqout")
      (footprint "eagle-import:1X01NS-KIT")
      (libsource (lib "eagle-import") (part "M01NOSILK-KIT"))
    )
    (comp (ref "J205")
      (value "eqout")
      (footprint "eagle-import:1X01NS-KIT")
      (libsource (lib "eagle-import") (part "M01NOSILK-KIT"))
    )
    (comp (ref "J206")
      (value "CONN_05PTH_LONGPADS")
      (footprint "eagle-import:1X05_LONGPADS")
      (libsource (lib "eagle-import") (part "CONN_05PTH_LONGPADS"))
    )
    (comp (ref "R201")
      (value "6k8")
      (footprint "eagle-import:AXIAL-0.3")
      (libsource (lib "eagle-import") (part "RESISTOR"))
    )
    (comp (ref "R202")
      (value "6k8")
      (footprint "eagle-import:AXIAL-0.3")
      (libsource (lib "eagle-import") (part "RESISTOR"))
    )
    (comp (ref "R203")
      (value "10")
      (footprint "eagle-import:AXIAL-0.3")
      (libsource (lib "eagle-import") (part "RESISTOR"))
    )
    (comp (ref "R204")
      (value "10")
      (footprint "eagle-import:AXIAL-0.3")
      (libsource (lib "eagle-import") (part "RESISTOR"))
    )
    (comp (ref "R205")
      (value "4k99")
      (footprint "eagle-import:AXIAL-0.3")
      (libsource (lib "eagle-import") (part "RESISTOR"))
    )
    (comp (ref "R206")
      (value "4k99")
      (footprint "eagle-import:AXIAL-0.3")
      (libsource (lib "eagle-import") (part "RESISTOR"))
    )
    (comp (ref "R207")
      (value "22k")
      (footprint "eagle-import:AXIAL-0.3")
      (libsource (lib "eagle-import") (part "RESISTOR"))
    )
    (comp (ref "R208")
      (value "1k2")
      (footprint "eagle-import:AXIAL-0.3")
      (libsource (lib "eagle-import") (part "RESISTOR"))
    )
    (comp (ref "R209")
      (value "1k2")
      (footprint "eagle-import:AXIAL-0.3")
      (libsource (lib "eagle-import") (part "RESISTOR"))
    )
    (comp (ref "R210")
      (value "5")
      (footprint "eagle-import:AXIAL-0.3")
      (libsource (lib "eagle-import") (part "RESISTOR"))
    )
    (comp (ref "R211")
      (value "1k8")
      (footprint "eagle-import:AXIAL-0.3")
      (libsource (lib "eagle-import") (part "RESISTOR"))
    )
    (comp (ref "R212")
      (value "1k8")
      (footprint "eagle-import:AXIAL-0.3")
      (libsource (lib "eagle-import") (part "RESISTOR"))
    )
    (comp (ref "R213")
      (value "12k")
      (footprint "eagle-import:AXIAL-0.3")
      (libsource (lib "eagle-import") (part "RESISTOR"))
    )
    (comp (ref "R214")
      (value "1k")
      (footprint "eagle-import:AXIAL-0.3")
      (libsource (lib "eagle-import") (part "RESISTOR"))
    )
    (comp (ref "R215")
      (value "1k")
      (footprint "eagle-import:AXIAL-0.3")
      (libsource (lib "eagle-import") (part "RESISTOR"))
    )
    (comp (ref "R216")
      (value "1k")
      (footprint "eagle-import:AXIAL-0.3")
      (libsource (lib "eagle-import") (part "RESISTOR"))
    )
    (comp (ref "U201")
      (value "lme49710")
      (footprint "eagle-import:DIP08-KIT")
      (libsource (lib "eagle-import") (part "OPAMPLME49710"))
    )
    (comp (ref "VR201")
      (value "10K")
      (footprint "eagle-import:ROT-SW-POT")
      (libsource (lib "eagle-import") (part "POTROT-SW-POT"))
    )
    (comp (ref "VR202")
      (value "10K")
      (footprint "eagle-import:ALPHA-RV24AF40-POT")
      (libsource (lib "eagle-import") (part "POT10K-VERTPIN"))
    )
    (comp (ref "VR203")
      (value "10K")
      (footprint "eagle-import:ALPHA-RV24AF40-POT")
      (libsource (lib "eagle-import") (part "POT10K-VERTPIN"))
    )
    (comp (ref "VR204")
      (value "10K")
      (footprint "eagle-import:ALPHA-RV24AF40-POT")
      (libsource (lib "eagle-import") (part "POT10K-VERTPIN"))
    )
    (comp (ref "VR205")
      (value "10K")
      (footprint "eagle-import:ALPHA-RV24AF40-POT")
      (libsource (lib "eagle-import") (part "POT10K-VERTPIN"))
    )
    (comp (ref "C1")
      (value "0.01uf")
      (footprint "eagle-import:WIMA-MKS2-2.5X7.2")
      (libsource (lib "eagle-import") (part "WIMA-MKS20.01UF"))
    )
    (comp (ref "C2")
      (value "0.01uf")
      (footprint "eagle-import:WIMA-MKS2-2.5X7.2")
      (libsource (lib "eagle-import") (part "WIMA-MKS20.01UF"))
    )
    (comp (ref "C5")
      (value "1uf/160V")
      (footprint "eagle-import:CAP-PANA-2.5LS-6DIAM")
      (libsource (lib "eagle-import") (part "CAP-LYTIC1UF/160V"))
    )
    (comp (ref "C6")
      (value "1uf/160V")
      (footprint "eagle-import:CAP-PANA-2.5LS-6DIAM")
      (libsource (lib "eagle-import") (part "CAP-LYTIC1UF/160V"))
    )
    (comp (ref "C601")
      (value "100pf")
      (footprint "eagle-import:CAP-KEMET-GM-2.54LS")
      (libsource (lib "eagle-import") (part "CAP-CERAMIC100PF"))
    )
    (comp (ref "C602")
      (value "47u/25V")
      (footprint "eagle-import:CAP-PANA-2LS-5DIAM")
      (libsource (lib "eagle-import") (part "CAP-LYTIC47U/25V"))
    )
    (comp (ref "C603")
      (value "0.01uf")
      (footprint "eagle-import:WIMA-MKS2-2.5X7.2")
      (libsource (lib "eagle-import") (part "WIMA-MKS20.01UF"))
    )
    (comp (ref "C604")
      (value "0.01uf")
      (footprint "eagle-import:WIMA-MKS2-2.5X7.2")
      (libsource (lib "eagle-import") (part "WIMA-MKS20.01UF"))
    )
    (comp (ref "C605")
      (value "100pf")
      (footprint "eagle-import:CAP-KEMET-GM-2.54LS")
      (libsource (lib "eagle-import") (part "CAP-CERAMIC100PF"))
    )
    (comp (ref "D1")
      (value "1n4148")
      (footprint "eagle-import:DIODE-1N4148")
      (libsource (lib "eagle-import") (part "DIODE-1N4148"))
    )
    (comp (ref "D2")
      (value "1n4148")
      (footprint "eagle-import:DIODE-1N4148")
      (libsource (lib "eagle-import") (part "DIODE-1N4148"))
    )
    (comp (ref "D601")
      (value "RECTIFIERRB15X")
      (footprint "eagle-import:SM-RECTIFIER")
      (libsource (lib "eagle-import") (part "RECTIFIERRB15X"))
    )
    (comp (ref "D602")
      (value "RED")
      (footprint "eagle-import:LED_BARGRAPH_10")
      (libsource (lib "eagle-import") (part "LED_BARGRAPH_10RED"))
    )
    (comp (ref "FB601")
      (value "FB")
      (footprint "eagle-import:BEAD")
      (libsource (lib "eagle-import") (part "FB"))
    )
    (comp (ref "FRAME601")
      (value "FRAME-LEDGER")
      (footprint "eagle-import:CREATIVE_COMMONS")
      (libsource (lib "eagle-import") (part "FRAME-LEDGER"))
    )
    (comp (ref "H601")
      (value "STAND-OFF")
      (footprint "eagle-import:STAND-OFF")
      (libsource (lib "eagle-import") (part "STAND-OFF"))
    )
    (comp (ref "H602")
      (value "STAND-OFF")
      (footprint "eagle-import:STAND-OFF")
      (libsource (lib "eagle-import") (part "STAND-OFF"))
    )
    (comp (ref "H603")
      (value "STAND-OFF")
      (footprint "eagle-import:STAND-OFF")
      (libsource (lib "eagle-import") (part "STAND-OFF"))
    )
    (comp (ref "H605")
      (value "STAND-OFF")
      (footprint "eagle-import:STAND-OFF")
      (libsource (lib "eagle-import") (part "STAND-OFF"))
    )
    (comp (ref "H612")
      (value "STAND-OFF")
      (footprint "eagle-import:STAND-OFF")
      (libsource (lib "eagle-import") (part "STAND-OFF"))
    )
    (comp (ref "J601")
      (value "out2")
      (footprint "eagle-import:1X02_LOCK_LONGPADS")
      (libsource (lib "eagle-import") (part "CONN_02LOCK_LONGPADS"))
    )
    (comp (ref "R1")
      (value "10k")
      (footprint "eagle-import:AXIAL-0.3")
      (libsource (lib "eagle-import") (part "RESISTOR"))
    )
    (comp (ref "R2")
      (value "100k")
      (footprint "eagle-import:AXIAL-0.3")
      (libsource (lib "eagle-import") (part "RESISTOR"))
    )
    (comp (ref "R3")
      (value "1k")
      (footprint "eagle-import:AXIAL-0.3")
      (libsource (lib "eagle-import") (part "RESISTOR"))
    )
    (comp (ref "R601")
      (value "10k")
      (footprint "eagle-import:AXIAL-0.3")
      (libsource (lib "eagle-import") (part "RESISTOR"))
    )
    (comp (ref "R602")
      (value "10k")
      (footprint "eagle-import:AXIAL-0.3")
      (libsource (lib "eagle-import") (part "RESISTOR"))
    )
    (comp (ref "R603")
      (value "10k")
      (footprint "eagle-import:AXIAL-0.3")
      (libsource (lib "eagle-import") (part "RESISTOR"))
    )
    (comp (ref "R604")
      (value "10k")
      (footprint "eagle-import:AXIAL-0.3")
      (libsource (lib "eagle-import") (part "RESISTOR"))
    )
    (comp (ref "R605")
      (value "10k")
      (footprint "eagle-import:AXIAL-0.3")
      (libsource (lib "eagle-import") (part "RESISTOR"))
    )
    (comp (ref "R606")
      (value "10k")
      (footprint "eagle-import:AXIAL-0.3")
      (libsource (lib "eagle-import") (part "RESISTOR"))
    )
    (comp (ref "R607")
      (value "100")
      (footprint "eagle-import:AXIAL-0.3")
      (libsource (lib "eagle-import") (part "RESISTOR"))
    )
    (comp (ref "R608")
      (value "47k")
      (footprint "eagle-import:AXIAL-0.3")
      (libsource (lib "eagle-import") (part "RESISTOR"))
    )
    (comp (ref "R609")
      (value "???")
      (footprint "eagle-import:AXIAL-0.3")
      (libsource (lib "eagle-import") (part "RESISTOR"))
    )
    (comp (ref "R610")
      (value "???")
      (footprint "eagle-import:AXIAL-0.3")
      (libsource (lib "eagle-import") (part "RESISTOR"))
    )
    (comp (ref "R611")
      (value "???")
      (footprint "eagle-import:AXIAL-0.3")
      (libsource (lib "eagle-import") (part "RESISTOR"))
    )
    (comp (ref "U1")
      (value "LM358")
      (footprint "eagle-import:DIP08")
      (libsource (lib "eagle-import") (part "LM358"))
    )
    (comp (ref "U601")
      (value "lme49710")
      (footprint "eagle-import:DIP08-KIT")
      (libsource (lib "eagle-import") (part "OPAMPLME49710"))
    )
    (comp (ref "U602")
      (value "LM3915N")
      (footprint "eagle-import:DIL18")
      (libsource (lib "eagle-import") (part "LM391N5"))
    )
    (comp (ref "C701")
      (value "1000u/35V")
      (footprint "eagle-import:CAP-PANA-5LS-12.5DIAM")
      (libsource (lib "eagle-import") (part "CAP-LYTIC1000U/35V"))
    )
    (comp (ref "C702")
      (value "1000u/35V")
      (footprint "eagle-import:CAP-PANA-5LS-12.5DIAM")
      (libsource (lib "eagle-import") (part "CAP-LYTIC1000U/35V"))
    )
    (comp (ref "D701")
      (value "LED5MM")
      (footprint "eagle-import:LED_5MM")
      (libsource (lib "eagle-import") (part "LED5MM"))
    )
    (comp (ref "FRAME701")
      (value "FRAME-LEDGER")
      (footprint "eagle-import:CREATIVE_COMMONS")
      (libsource (lib "eagle-import") (part "FRAME-LEDGER"))
    )
    (comp (ref "J701")
      (value "power")
      (footprint "eagle-import:MOLEX-1X3_LOCK")
      (libsource (lib "eagle-import") (part "CONN_03POLAR_LOCK"))
    )
    (comp (ref "R701")
      (value "10")
      (footprint "eagle-import:AXIAL-0.3")
      (libsource (lib "eagle-import") (part "RESISTORAXIAL-0.3"))
    )
    (comp (ref "R702")
      (value "10")
      (footprint "eagle-import:AXIAL-0.3")
      (libsource (lib "eagle-import") (part "RESISTORAXIAL-0.3"))
    )
    (comp (ref "R703")
      (value "1k5")
      (footprint "eagle-import:AXIAL-0.3")
      (libsource (lib "eagle-import") (part "RESISTORAXIAL-0.3"))
    )
    (comp (ref "C401")
      (value "47pf")
      (footprint "eagle-import:CAP-KEMET-GM-2.54LS")
      (libsource (lib "eagle-import") (part "CAP-CERAMIC47PF"))
    )
    (comp (ref "C402")
      (value "47pf")
      (footprint "eagle-import:CAP-KEMET-GM-2.54LS")
      (libsource (lib "eagle-import") (part "CAP-CERAMIC47PF"))
    )
    (comp (ref "C403")
      (value "470pf")
      (footprint "eagle-import:CAP-KEMET-GM-2.54LS")
      (libsource (lib "eagle-import") (part "CAP-CERAMIC470PF"))
    )
    (comp (ref "C404")
      (value "470pf")
      (footprint "eagle-import:CAP-KEMET-GM-2.54LS")
      (libsource (lib "eagle-import") (part "CAP-CERAMIC470PF"))
    )
    (comp (ref "C405")
      (value "470pf")
      (footprint "eagle-import:CAP-KEMET-GM-2.54LS")
      (libsource (lib "eagle-import") (part "CAP-CERAMIC470PF"))
    )
    (comp (ref "C406")
      (value "470pf")
      (footprint "eagle-import:CAP-KEMET-GM-2.54LS")
      (libsource (lib "eagle-import") (part "CAP-CERAMIC470PF"))
    )
    (comp (ref "C407")
      (value "47u/63V")
      (footprint "eagle-import:CAP-PANA-2LS-6DIAM")
      (libsource (lib "eagle-import") (part "CAP-LYTIC47U/63V"))
    )
    (comp (ref "C408")
      (value "47u/63V")
      (footprint "eagle-import:CAP-PANA-2LS-6DIAM")
      (libsource (lib "eagle-import") (part "CAP-LYTIC47U/63V"))
    )
    (comp (ref "C409")
      (value "47u/25V")
      (footprint "eagle-import:CAP-PANA-2LS-5DIAM")
      (libsource (lib "eagle-import") (part "CAP-LYTIC47U/25V"))
    )
    (comp (ref "C410")
      (value "47u/25V")
      (footprint "eagle-import:CAP-PANA-2LS-5DIAM")
      (libsource (lib "eagle-import") (part "CAP-LYTIC47U/25V"))
    )
    (comp (ref "C411")
      (value "6800u/25V")
      (footprint "eagle-import:CAP-PANA-5LS-12.5DIAM")
      (libsource (lib "eagle-import") (part "CAP-LYTIC6800U/10V"))
    )
    (comp (ref "C412")
      (value "470pf")
      (footprint "eagle-import:CAP-KEMET-GM-2.54LS")
      (libsource (lib "eagle-import") (part "CAP-CERAMIC470PF"))
    )
    (comp (ref "C413")
      (value "470pf")
      (footprint "eagle-import:CAP-KEMET-GM-2.54LS")
      (libsource (lib "eagle-import") (part "CAP-CERAMIC470PF"))
    )
    (comp (ref "C414")
      (value "47u/25V")
      (footprint "eagle-import:CAP-PANA-2LS-5DIAM")
      (libsource (lib "eagle-import") (part "CAP-LYTIC47U/25V"))
    )
    (comp (ref "C415")
      (value "0.1uf")
      (footprint "eagle-import:WIMA-MKS2-2.5X7.2")
      (libsource (lib "eagle-import") (part "WIMA-MKS20.1UF"))
    )
    (comp (ref "C416")
      (value "0.1uf")
      (footprint "eagle-import:WIMA-MKS2-2.5X7.2")
      (libsource (lib "eagle-import") (part "WIMA-MKS20.1UF"))
    )
    (comp (ref "C417")
      (value "0.015uf")
      (footprint "eagle-import:WIMA-MKS2-2.5X7.2")
      (libsource (lib "eagle-import") (part "WIMA-MKS20.015UF"))
    )
    (comp (ref "C418")
      (value "0.015uf")
      (footprint "eagle-import:WIMA-MKS2-2.5X7.2")
      (libsource (lib "eagle-import") (part "WIMA-MKS20.015UF"))
    )
    (comp (ref "C419")
      (value "100pf")
      (footprint "eagle-import:CAP-KEMET-GM-2.54LS")
      (libsource (lib "eagle-import") (part "CAP-CERAMIC100PF"))
    )
    (comp (ref "C420")
      (value "47u/25V")
      (footprint "eagle-import:CAP-PANA-2LS-5DIAM")
      (libsource (lib "eagle-import") (part "CAP-LYTIC47U/25V"))
    )
    (comp (ref "C421")
      (value "0.01uf")
      (footprint "eagle-import:WIMA-MKS2-2.5X7.2")
      (libsource (lib "eagle-import") (part "WIMA-MKS20.01UF"))
    )
    (comp (ref "C422")
      (value "0.01uf")
      (footprint "eagle-import:WIMA-MKS2-2.5X7.2")
      (libsource (lib "eagle-import") (part "WIMA-MKS20.01UF"))
    )
    (comp (ref "D401")
      (value "RECTIFIERRB15X")
      (footprint "eagle-import:SM-RECTIFIER")
      (libsource (lib "eagle-import") (part "RECTIFIERRB15X"))
    )
    (comp (ref "D402")
      (value "200mA/100V/1V")
      (footprint "eagle-import:DIODE-1N4148")
      (libsource (lib "eagle-import") (part "DIODE-1N4148"))
    )
    (comp (ref "D403")
      (value "200mA/100V/1V")
      (footprint "eagle-import:DIODE-1N4148")
      (libsource (lib "eagle-import") (part "DIODE-1N4148"))
    )
    (comp (ref "FRAME401")
      (value "FRAME-LEDGER")
      (footprint "eagle-import:CREATIVE_COMMONS")
      (libsource (lib "eagle-import") (part "FRAME-LEDGER"))
    )
    (comp (ref "IC401")
      (value "THAT1512")
      (footprint "eagle-import:DIP08-KIT")
      (libsource (lib "eagle-import") (part "THAT151X"))
    )
    (comp (ref "J401")
      (value "M031X03_NO_SILK")
      (footprint "eagle-import:1X03_NO_SILK@1")
      (libsource (lib "eagle-import") (part "M031X03_NO_SILK"))
    )
    (comp (ref "J402")
      (value "M031X03_NO_SILK")
      (footprint "eagle-import:1X03_NO_SILK@1")
      (libsource (lib "eagle-import") (part "M031X03_NO_SILK"))
    )
    (comp (ref "J403")
      (value "phantom")
      (footprint "eagle-import:1X01NS-KIT")
      (libsource (lib "eagle-import") (part "M01NOSILK-KIT"))
    )
    (comp (ref "J404")
      (value "eqout")
      (footprint "eagle-import:1X01NS-KIT")
      (libsource (lib "eagle-import") (part "M01NOSILK-KIT"))
    )
    (comp (ref "J405")
      (value "eqout")
      (footprint "eagle-import:1X01NS-KIT")
      (libsource (lib "eagle-import") (part "M01NOSILK-KIT"))
    )
    (comp (ref "J406")
      (value "CONN_05PTH_LONGPADS")
      (footprint "eagle-import:1X05_LONGPADS")
      (libsource (lib "eagle-import") (part "CONN_05PTH_LONGPADS"))
    )
    (comp (ref "R401")
      (value "6k8")
      (footprint "eagle-import:AXIAL-0.3")
      (libsource (lib "eagle-import") (part "RESISTOR"))
    )
    (comp (ref "R402")
      (value "6k8")
      (footprint "eagle-import:AXIAL-0.3")
      (libsource (lib "eagle-import") (part "RESISTOR"))
    )
    (comp (ref "R403")
      (value "10")
      (footprint "eagle-import:AXIAL-0.3")
      (libsource (lib "eagle-import") (part "RESISTOR"))
    )
    (comp (ref "R404")
      (value "10")
      (footprint "eagle-import:AXIAL-0.3")
      (libsource (lib "eagle-import") (part "RESISTOR"))
    )
    (comp (ref "R405")
      (value "4k99")
      (footprint "eagle-import:AXIAL-0.3")
      (libsource (lib "eagle-import") (part "RESISTOR"))
    )
    (comp (ref "R406")
      (value "4k99")
      (footprint "eagle-import:AXIAL-0.3")
      (libsource (lib "eagle-import") (part "RESISTOR"))
    )
    (comp (ref "R407")
      (value "22k")
      (footprint "eagle-import:AXIAL-0.3")
      (libsource (lib "eagle-import") (part "RESISTOR"))
    )
    (comp (ref "R408")
      (value "1k2")
      (footprint "eagle-import:AXIAL-0.3")
      (libsource (lib "eagle-import") (part "RESISTOR"))
    )
    (comp (ref "R409")
      (value "1k2")
      (footprint "eagle-import:AXIAL-0.3")
      (libsource (lib "eagle-import") (part "RESISTOR"))
    )
    (comp (ref "R410")
      (value "5")
      (footprint "eagle-import:AXIAL-0.3")
      (libsource (lib "eagle-import") (part "RESISTOR"))
    )
    (comp (ref "R411")
      (value "1k8")
      (footprint "eagle-import:AXIAL-0.3")
      (libsource (lib "eagle-import") (part "RESISTOR"))
    )
    (comp (ref "R412")
      (value "1k8")
      (footprint "eagle-import:AXIAL-0.3")
      (libsource (lib "eagle-import") (part "RESISTOR"))
    )
    (comp (ref "R413")
      (value "12k")
      (footprint "eagle-import:AXIAL-0.3")
      (libsource (lib "eagle-import") (part "RESISTOR"))
    )
    (comp (ref "R414")
      (value "1k")
      (footprint "eagle-import:AXIAL-0.3")
      (libsource (lib "eagle-import") (part "RESISTOR"))
    )
    (comp (ref "R415")
      (value "1k")
      (footprint "eagle-import:AXIAL-0.3")
      (libsource (lib "eagle-import") (part "RESISTOR"))
    )
    (comp (ref "R416")
      (value "1k")
      (footprint "eagle-import:AXIAL-0.3")
      (libsource (lib "eagle-import") (part "RESISTOR"))
    )
    (comp (ref "U401")
      (value "lme49710")
      (footprint "eagle-import:DIP08-KIT")
      (libsource (lib "eagle-import") (part "OPAMPLME49710"))
    )
    (comp (ref "VR401")
      (value "10K")
      (footprint "eagle-import:ROT-SW-POT")
      (libsource (lib "eagle-import") (part "POTROT-SW-POT"))
    )
    (comp (ref "VR402")
      (value "10K")
      (footprint "eagle-import:ALPHA-RV24AF40-POT")
      (libsource (lib "eagle-import") (part "POT10K-VERTPIN"))
    )
    (comp (ref "VR403")
      (value "10K")
      (footprint "eagle-import:ALPHA-RV24AF40-POT")
      (libsource (lib "eagle-import") (part "POT10K-VERTPIN"))
    )
    (comp (ref "VR404")
      (value "10K")
      (footprint "eagle-import:ALPHA-RV24AF40-POT")
      (libsource (lib "eagle-import") (part "POT10K-VERTPIN"))
    )
    (comp (ref "VR405")
      (value "10K")
      (footprint "eagle-import:ALPHA-RV24AF40-POT")
      (libsource (lib "eagle-import") (part "POT10K-VERTPIN"))
    )
    (comp (ref "C3")
      (value "1uf/160V")
      (footprint "eagle-import:CAP-PANA-2.5LS-6DIAM")
      (libsource (lib "eagle-import") (part "CAP-LYTIC1UF/160V"))
    )
    (comp (ref "C4")
      (value "1uf/160V")
      (footprint "eagle-import:CAP-PANA-2.5LS-6DIAM")
      (libsource (lib "eagle-import") (part "CAP-LYTIC1UF/160V"))
    )
    (comp (ref "C501")
      (value "100pf")
      (footprint "eagle-import:CAP-KEMET-GM-2.54LS")
      (libsource (lib "eagle-import") (part "CAP-CERAMIC100PF"))
    )
    (comp (ref "C502")
      (value "47u/25V")
      (footprint "eagle-import:CAP-PANA-2LS-5DIAM")
      (libsource (lib "eagle-import") (part "CAP-LYTIC47U/25V"))
    )
    (comp (ref "C503")
      (value "0.01uf")
      (footprint "eagle-import:WIMA-MKS2-2.5X7.2")
      (libsource (lib "eagle-import") (part "WIMA-MKS20.01UF"))
    )
    (comp (ref "C504")
      (value "0.01uf")
      (footprint "eagle-import:WIMA-MKS2-2.5X7.2")
      (libsource (lib "eagle-import") (part "WIMA-MKS20.01UF"))
    )
    (comp (ref "C505")
      (value "100pf")
      (footprint "eagle-import:CAP-KEMET-GM-2.54LS")
      (libsource (lib "eagle-import") (part "CAP-CERAMIC100PF"))
    )
    (comp (ref "D3")
      (value "1n4148")
      (footprint "eagle-import:DIODE-1N4148")
      (libsource (lib "eagle-import") (part "DIODE-1N4148"))
    )
    (comp (ref "D4")
      (value "1n4148")
      (footprint "eagle-import:DIODE-1N4148")
      (libsource (lib "eagle-import") (part "DIODE-1N4148"))
    )
    (comp (ref "D501")
      (value "RECTIFIERRB15X")
      (footprint "eagle-import:SM-RECTIFIER")
      (libsource (lib "eagle-import") (part "RECTIFIERRB15X"))
    )
    (comp (ref "D502")
      (value "RED")
      (footprint "eagle-import:LED_BARGRAPH_10")
      (libsource (lib "eagle-import") (part "LED_BARGRAPH_10RED"))
    )
    (comp (ref "FB501")
      (value "FB")
      (footprint "eagle-import:BEAD")
      (libsource (lib "eagle-import") (part "FB"))
    )
    (comp (ref "FRAME501")
      (value "FRAME-LEDGER")
      (footprint "eagle-import:CREATIVE_COMMONS")
      (libsource (lib "eagle-import") (part "FRAME-LEDGER"))
    )
    (comp (ref "J501")
      (value "out2")
      (footprint "eagle-import:1X02_LOCK_LONGPADS")
      (libsource (lib "eagle-import") (part "CONN_02LOCK_LONGPADS"))
    )
    (comp (ref "R4")
      (value "10k")
      (footprint "eagle-import:AXIAL-0.3")
      (libsource (lib "eagle-import") (part "RESISTOR"))
    )
    (comp (ref "R5")
      (value "100k")
      (footprint "eagle-import:AXIAL-0.3")
      (libsource (lib "eagle-import") (part "RESISTOR"))
    )
    (comp (ref "R6")
      (value "1k")
      (footprint "eagle-import:AXIAL-0.3")
      (libsource (lib "eagle-import") (part "RESISTOR"))
    )
    (comp (ref "R501")
      (value "10k")
      (footprint "eagle-import:AXIAL-0.3")
      (libsource (lib "eagle-import") (part "RESISTOR"))
    )
    (comp (ref "R502")
      (value "10k")
      (footprint "eagle-import:AXIAL-0.3")
      (libsource (lib "eagle-import") (part "RESISTOR"))
    )
    (comp (ref "R503")
      (value "10k")
      (footprint "eagle-import:AXIAL-0.3")
      (libsource (lib "eagle-import") (part "RESISTOR"))
    )
    (comp (ref "R504")
      (value "10k")
      (footprint "eagle-import:AXIAL-0.3")
      (libsource (lib "eagle-import") (part "RESISTOR"))
    )
    (comp (ref "R505")
      (value "10k")
      (footprint "eagle-import:AXIAL-0.3")
      (libsource (lib "eagle-import") (part "RESISTOR"))
    )
    (comp (ref "R506")
      (value "10k")
      (footprint "eagle-import:AXIAL-0.3")
      (libsource (lib "eagle-import") (part "RESISTOR"))
    )
    (comp (ref "R507")
      (value "100")
      (footprint "eagle-import:AXIAL-0.3")
      (libsource (lib "eagle-import") (part "RESISTOR"))
    )
    (comp (ref "R508")
      (value "47k")
      (footprint "eagle-import:AXIAL-0.3")
      (libsource (lib "eagle-import") (part "RESISTOR"))
    )
    (comp (ref "R509")
      (value "???")
      (footprint "eagle-import:AXIAL-0.3")
      (libsource (lib "eagle-import") (part "RESISTOR"))
    )
    (comp (ref "R510")
      (value "???")
      (footprint "eagle-import:AXIAL-0.3")
      (libsource (lib "eagle-import") (part "RESISTOR"))
    )
    (comp (ref "R511")
      (value "???")
      (footprint "eagle-import:AXIAL-0.3")
      (libsource (lib "eagle-import") (part "RESISTOR"))
    )
    (comp (ref "U501")
      (value "lme49710")
      (footprint "eagle-import:DIP08-KIT")
      (libsource (lib "eagle-import") (part "OPAMPLME49710"))
    )
    (comp (ref "U502")
      (value "LM3915N")
      (footprint "eagle-import:DIL18")
      (libsource (lib "eagle-import") (part "LM391N5"))
    )
  )
  (nets
    (net (code "1") (name "1TO1") (class "Default")
      (node (ref "J106") (pin "2") (pinfunction "2_2") (pintype "passive"))
      (node (ref "R501") (pin "P$2") (pinfunction "2_P$2") (pintype "passive"))
    )
    (net (code "2") (name "1TO2") (class "Default")
      (node (ref "J106") (pin "3") (pinfunction "3_3") (pintype "passive"))
      (node (ref "R601") (pin "P$2") (pinfunction "2_P$2") (pintype "passive"))
    )
    (net (code "3") (name "2TO1") (class "Default")
      (node (ref "J206") (pin "2") (pinfunction "2_2") (pintype "passive"))
      (node (ref "R502") (pin "P$2") (pinfunction "2_P$2") (pintype "passive"))
    )
    (net (code "4") (name "2TO2") (class "Default")
      (node (ref "J206") (pin "3") (pinfunction "3_3") (pintype "passive"))
      (node (ref "R602") (pin "P$2") (pinfunction "2_P$2") (pintype "passive"))
    )
    (net (code "5") (name "3TO1") (class "Default")
      (node (ref "J306") (pin "2") (pinfunction "2_2") (pintype "passive"))
      (node (ref "R503") (pin "P$2") (pinfunction "2_P$2") (pintype "passive"))
    )
    (net (code "6") (name "3TO2") (class "Default")
      (node (ref "J306") (pin "3") (pinfunction "3_3") (pintype "passive"))
      (node (ref "R603") (pin "P$2") (pinfunction "2_P$2") (pintype "passive"))
    )
    (net (code "7") (name "4TO1") (class "Default")
      (node (ref "J406") (pin "2") (pinfunction "2_2") (pintype "passive"))
      (node (ref "R504") (pin "P$2") (pinfunction "2_P$2") (pintype "passive"))
    )
    (net (code "8") (name "4TO2") (class "Default")
      (node (ref "J406") (pin "3") (pinfunction "3_3") (pintype "passive"))
      (node (ref "R604") (pin "P$2") (pinfunction "2_P$2") (pintype "passive"))
    )
    (net (code "9") (name "GND") (class "Default")
      (node (ref "C1") (pin "P$1") (pinfunction "1_P$1") (pintype "passive"))
      (node (ref "C112") (pin "P$2") (pinfunction "2_P$2") (pintype "passive"))
      (node (ref "C113") (pin "P$2") (pinfunction "2_P$2") (pintype "passive"))
      (node (ref "C121") (pin "P$2") (pinfunction "2_P$2") (pintype "passive"))
      (node (ref "C122") (pin "P$1") (pinfunction "1_P$1") (pintype "passive"))
      (node (ref "C2") (pin "P$2") (pinfunction "2_P$2") (pintype "passive"))
      (node (ref "C212") (pin "P$2") (pinfunction "2_P$2") (pintype "passive"))
      (node (ref "C213") (pin "P$2") (pinfunction "2_P$2") (pintype "passive"))
      (node (ref "C221") (pin "P$2") (pinfunction "2_P$2") (pintype "passive"))
      (node (ref "C222") (pin "P$1") (pinfunction "1_P$1") (pintype "passive"))
      (node (ref "C312") (pin "P$2") (pinfunction "2_P$2") (pintype "passive"))
      (node (ref "C313") (pin "P$2") (pinfunction "2_P$2") (pintype "passive"))
      (node (ref "C321") (pin "P$2") (pinfunction "2_P$2") (pintype "passive"))
      (node (ref "C322") (pin "P$1") (pinfunction "1_P$1") (pintype "passive"))
      (node (ref "C4") (pin "NEG") (pinfunction "-_NEG") (pintype "passive"))
      (node (ref "C412") (pin "P$2") (pinfunction "2_P$2") (pintype "passive"))
      (node (ref "C413") (pin "P$2") (pinfunction "2_P$2") (pintype "passive"))
      (node (ref "C421") (pin "P$2") (pinfunction "2_P$2") (pintype "passive"))
      (node (ref "C422") (pin "P$1") (pinfunction "1_P$1") (pintype "passive"))
      (node (ref "C503") (pin "P$2") (pinfunction "2_P$2") (pintype "passive"))
      (node (ref "C504") (pin "P$1") (pinfunction "1_P$1") (pintype "passive"))
      (node (ref "C505") (pin "P$2") (pinfunction "2_P$2") (pintype "passive"))
      (node (ref "C6") (pin "NEG") (pinfunction "-_NEG") (pintype "passive"))
      (node (ref "C603") (pin "P$2") (pinfunction "2_P$2") (pintype "passive"))
      (node (ref "C604") (pin "P$1") (pinfunction "1_P$1") (pintype "passive"))
      (node (ref "C605") (pin "P$2") (pinfunction "2_P$2") (pintype "passive"))
      (node (ref "C701") (pin "NEG") (pinfunction "-_NEG") (pintype "passive"))
      (node (ref "C702") (pin "POS") (pinfunction "+_POS") (pintype "passive"))
      (node (ref "D701") (pin "K") (pinfunction "C_K") (pintype "passive"))
      (node (ref "IC101") (pin "5") (pinfunction "REF_5") (pintype "bidirectional"))
      (node (ref "IC201") (pin "5") (pinfunction "REF_5") (pintype "bidirectional"))
      (node (ref "IC301") (pin "5") (pinfunction "REF_5") (pintype "bidirectional"))
      (node (ref "IC401") (pin "5") (pinfunction "REF_5") (pintype "bidirectional"))
      (node (ref "J106") (pin "4") (pinfunction "4_4") (pintype "passive"))
      (node (ref "J106") (pin "5") (pinfunction "5_5") (pintype "passive"))
      (node (ref "J206") (pin "4") (pinfunction "4_4") (pintype "passive"))
      (node (ref "J206") (pin "5") (pinfunction "5_5") (pintype "passive"))
      (node (ref "J306") (pin "4") (pinfunction "4_4") (pintype "passive"))
      (node (ref "J306") (pin "5") (pinfunction "5_5") (pintype "passive"))
      (node (ref "J406") (pin "4") (pinfunction "4_4") (pintype "passive"))
      (node (ref "J406") (pin "5") (pinfunction "5_5") (pintype "passive"))
      (node (ref "J501") (pin "2") (pinfunction "2_2") (pintype "passive"))
      (node (ref "J601") (pin "2") (pinfunction "2_2") (pintype "passive"))
      (node (ref "J701") (pin "2") (pinfunction "2_2") (pintype "passive"))
      (node (ref "R107") (pin "P$2") (pinfunction "2_P$2") (pintype "passive"))
      (node (ref "R207") (pin "P$2") (pinfunction "2_P$2") (pintype "passive"))
      (node (ref "R307") (pin "P$2") (pinfunction "2_P$2") (pintype "passive"))
      (node (ref "R407") (pin "P$2") (pinfunction "2_P$2") (pintype "passive"))
      (node (ref "R505") (pin "P$1") (pinfunction "1_P$1") (pintype "passive"))
      (node (ref "R508") (pin "P$2") (pinfunction "2_P$2") (pintype "passive"))
      (node (ref "R509") (pin "P$2") (pinfunction "2_P$2") (pintype "passive"))
      (node (ref "R605") (pin "P$1") (pinfunction "1_P$1") (pintype "passive"))
      (node (ref "R608") (pin "P$2") (pinfunction "2_P$2") (pintype "passive"))
      (node (ref "R609") (pin "P$2") (pinfunction "2_P$2") (pintype "passive"))
      (node (ref "U1") (pin "3") (pinfunction "+IN_3") (pintype "input"))
      (node (ref "U1") (pin "5") (pinfunction "+IN_5") (pintype "input"))
      (node (ref "U101") (pin "3") (pinfunction "+IN_3") (pintype "input"))
      (node (ref "U201") (pin "3") (pinfunction "+IN_3") (pintype "input"))
      (node (ref "U301") (pin "3") (pinfunction "+IN_3") (pintype "input"))
      (node (ref "U401") (pin "3") (pinfunction "+IN_3") (pintype "input"))
      (node (ref "U502") (pin "2") (pinfunction "V-_2") (pintype "power_in"))
      (node (ref "U502") (pin "4") (pinfunction "RLO_4") (pintype "input"))
      (node (ref "U602") (pin "2") (pinfunction "V-_2") (pintype "power_in"))
      (node (ref "U602") (pin "4") (pinfunction "RLO_4") (pintype "input"))
      (node (ref "VR104") (pin "CCW") (pinfunction "A_CCW") (pintype "passive"))
      (node (ref "VR105") (pin "CCW") (pinfunction "A_CCW") (pintype "passive"))
      (node (ref "VR204") (pin "CCW") (pinfunction "A_CCW") (pintype "passive"))
      (node (ref "VR205") (pin "CCW") (pinfunction "A_CCW") (pintype "passive"))
      (node (ref "VR304") (pin "CCW") (pinfunction "A_CCW") (pintype "passive"))
      (node (ref "VR305") (pin "CCW") (pinfunction "A_CCW") (pintype "passive"))
      (node (ref "VR404") (pin "CCW") (pinfunction "A_CCW") (pintype "passive"))
      (node (ref "VR405") (pin "CCW") (pinfunction "A_CCW") (pintype "passive"))
    )
    (net (code "10") (name "Net-(C3-+)") (class "Default")
      (node (ref "C3") (pin "POS") (pinfunction "+_POS") (pintype "passive"))
      (node (ref "C502") (pin "NEG") (pinfunction "-_NEG") (pintype "passive"))
      (node (ref "D501") (pin "AC1") (pinfunction "~_AC1") (pintype "bidirectional"))
      (node (ref "D501") (pin "AC2") (pinfunction "~{2}_AC2") (pintype "bidirectional"))
      (node (ref "FB501") (pin "P$1") (pinfunction "1_P$1") (pintype "passive"))
      (node (ref "R508") (pin "P$1") (pinfunction "1_P$1") (pintype "passive"))
    )
    (net (code "11") (name "Net-(C3--)") (class "Default")
      (node (ref "C3") (pin "NEG") (pinfunction "-_NEG") (pintype "passive"))
      (node (ref "R4") (pin "P$1") (pinfunction "1_P$1") (pintype "passive"))
    )
    (net (code "12") (name "Net-(C4-+)") (class "Default")
      (node (ref "C4") (pin "POS") (pinfunction "+_POS") (pintype "passive"))
      (node (ref "R6") (pin "P$2") (pinfunction "2_P$2") (pintype "passive"))
      (node (ref "U502") (pin "5") (pinfunction "SIGIN_5") (pintype "input"))
    )
    (net (code "13") (name "Net-(C5-+)") (class "Default")
      (node (ref "C5") (pin "POS") (pinfunction "+_POS") (pintype "passive"))
      (node (ref "C602") (pin "NEG") (pinfunction "-_NEG") (pintype "passive"))
      (node (ref "D601") (pin "AC1") (pinfunction "~_AC1") (pintype "bidirectional"))
      (node (ref "D601") (pin "AC2") (pinfunction "~{2}_AC2") (pintype "bidirectional"))
      (node (ref "FB601") (pin "P$1") (pinfunction "1_P$1") (pintype "passive"))
      (node (ref "R608") (pin "P$1") (pinfunction "1_P$1") (pintype "passive"))
    )
    (net (code "14") (name "Net-(C5--)") (class "Default")
      (node (ref "C5") (pin "NEG") (pinfunction "-_NEG") (pintype "passive"))
      (node (ref "R1") (pin "P$1") (pinfunction "1_P$1") (pintype "passive"))
    )
    (net (code "15") (name "Net-(C6-+)") (class "Default")
      (node (ref "C6") (pin "POS") (pinfunction "+_POS") (pintype "passive"))
      (node (ref "R3") (pin "P$2") (pinfunction "2_P$2") (pintype "passive"))
      (node (ref "U602") (pin "5") (pinfunction "SIGIN_5") (pintype "input"))
    )
    (net (code "16") (name "Net-(C101-1)") (class "Default")
      (node (ref "C101") (pin "P$1") (pinfunction "1_P$1") (pintype "passive"))
      (node (ref "J101") (pin "2") (pinfunction "2_2") (pintype "passive"))
    )
    (net (code "17") (name "Net-(C101-2)") (class "Default")
      (node (ref "C101") (pin "P$2") (pinfunction "2_P$2") (pintype "passive"))
      (node (ref "C103") (pin "P$2") (pinfunction "2_P$2") (pintype "passive"))
      (node (ref "C104") (pin "P$1") (pinfunction "1_P$1") (pintype "passive"))
    )
    (net (code "18") (name "Net-(C102-1)") (class "Default")
      (node (ref "C102") (pin "P$1") (pinfunction "1_P$1") (pintype "passive"))
      (node (ref "J102") (pin "2") (pinfunction "2_2") (pintype "passive"))
    )
    (net (code "19") (name "Net-(C102-2)") (class "Default")
      (node (ref "C102") (pin "P$2") (pinfunction "2_P$2") (pintype "passive"))
      (node (ref "C105") (pin "P$2") (pinfunction "2_P$2") (pintype "passive"))
      (node (ref "C106") (pin "P$1") (pinfunction "1_P$1") (pintype "passive"))
    )
    (net (code "20") (name "Net-(C103-1)") (class "Default")
      (node (ref "C103") (pin "P$1") (pinfunction "1_P$1") (pintype "passive"))
      (node (ref "C107") (pin "POS") (pinfunction "+_POS") (pintype "passive"))
      (node (ref "J101") (pin "3") (pinfunction "3_3") (pintype "passive"))
      (node (ref "R101") (pin "P$1") (pinfunction "1_P$1") (pintype "passive"))
    )
    (net (code "21") (name "Net-(C104-2)") (class "Default")
      (node (ref "C104") (pin "P$2") (pinfunction "2_P$2") (pintype "passive"))
      (node (ref "C108") (pin "POS") (pinfunction "+_POS") (pintype "passive"))
      (node (ref "J101") (pin "1") (pinfunction "1_1") (pintype "passive"))
      (node (ref "R102") (pin "P$1") (pinfunction "1_P$1") (pintype "passive"))
    )
    (net (code "22") (name "Net-(C105-1)") (class "Default")
      (node (ref "C105") (pin "P$1") (pinfunction "1_P$1") (pintype "passive"))
      (node (ref "C109") (pin "POS") (pinfunction "+_POS") (pintype "passive"))
      (node (ref "J102") (pin "3") (pinfunction "3_3") (pintype "passive"))
    )
    (net (code "23") (name "Net-(C106-2)") (class "Default")
      (node (ref "C106") (pin "P$2") (pinfunction "2_P$2") (pintype "passive"))
      (node (ref "C110") (pin "POS") (pinfunction "+_POS") (pintype "passive"))
      (node (ref "J102") (pin "1") (pinfunction "1_1") (pintype "passive"))
    )
    (net (code "24") (name "Net-(C107--)") (class "Default")
      (node (ref "C107") (pin "NEG") (pinfunction "-_NEG") (pintype "passive"))
      (node (ref "R103") (pin "P$2") (pinfunction "2_P$2") (pintype "passive"))
    )
    (net (code "25") (name "Net-(C108--)") (class "Default")
      (node (ref "C108") (pin "NEG") (pinfunction "-_NEG") (pintype "passive"))
      (node (ref "R104") (pin "P$2") (pinfunction "2_P$2") (pintype "passive"))
    )
    (net (code "26") (name "Net-(C109--)") (class "Default")
      (node (ref "C109") (pin "NEG") (pinfunction "-_NEG") (pintype "passive"))
      (node (ref "R105") (pin "P$2") (pinfunction "2_P$2") (pintype "passive"))
    )
    (net (code "27") (name "Net-(C110--)") (class "Default")
      (node (ref "C110") (pin "NEG") (pinfunction "-_NEG") (pintype "passive"))
      (node (ref "R106") (pin "P$2") (pinfunction "2_P$2") (pintype "passive"))
    )
    (net (code "28") (name "Net-(C111-+)") (class "Default")
      (node (ref "C111") (pin "POS") (pinfunction "+_POS") (pintype "passive"))
      (node (ref "R110") (pin "P$2") (pinfunction "2_P$2") (pintype "passive"))
    )
    (net (code "29") (name "Net-(C111--)") (class "Default")
      (node (ref "C111") (pin "NEG") (pinfunction "-_NEG") (pintype "passive"))
      (node (ref "D103") (pin "A") (pinfunction "A_A") (pintype "passive"))
      (node (ref "IC101") (pin "8") (pinfunction "RG2_8") (pintype "bidirectional"))
    )
    (net (code "30") (name "Net-(C114-+)") (class "Default")
      (node (ref "C114") (pin "POS") (pinfunction "+_POS") (pintype "passive"))
      (node (ref "IC101") (pin "6") (pinfunction "OUT_6") (pintype "bidirectional"))
    )
    (net (code "31") (name "Net-(C114--)") (class "Default")
      (node (ref "C114") (pin "NEG") (pinfunction "-_NEG") (pintype "passive"))
      (node (ref "J104") (pin "1") (pinfunction "1_1") (pintype "passive"))
      (node (ref "R112") (pin "P$1") (pinfunction "1_P$1") (pintype "passive"))
      (node (ref "R116") (pin "P$1") (pinfunction "1_P$1") (pintype "passive"))
    )
    (net (code "32") (name "Net-(C115-1)") (class "Default")
      (node (ref "C115") (pin "P$1") (pinfunction "1_P$1") (pintype "passive"))
      (node (ref "R111") (pin "P$1") (pinfunction "1_P$1") (pintype "passive"))
      (node (ref "VR102") (pin "CCW") (pinfunction "A_CCW") (pintype "passive"))
    )
    (net (code "33") (name "Net-(C115-2)") (class "Default")
      (node (ref "C115") (pin "P$2") (pinfunction "2_P$2") (pintype "passive"))
      (node (ref "C116") (pin "P$2") (pinfunction "2_P$2") (pintype "passive"))
      (node (ref "R113") (pin "P$2") (pinfunction "2_P$2") (pintype "passive"))
      (node (ref "VR102") (pin "WIP") (pinfunction "S_WIP") (pintype "passive"))
    )
    (net (code "34") (name "Net-(C116-1)") (class "Default")
      (node (ref "C116") (pin "P$1") (pinfunction "1_P$1") (pintype "passive"))
      (node (ref "R112") (pin "P$2") (pinfunction "2_P$2") (pintype "passive"))
      (node (ref "VR102") (pin "CW") (pinfunction "E_CW") (pintype "passive"))
    )
    (net (code "35") (name "Net-(C117-1)") (class "Default")
      (node (ref "C117") (pin "P$1") (pinfunction "1_P$1") (pintype "passive"))
      (node (ref "R115") (pin "P$1") (pinfunction "1_P$1") (pintype "passive"))
    )
    (net (code "36") (name "Net-(C117-2)") (class "Default")
      (node (ref "C117") (pin "P$2") (pinfunction "2_P$2") (pintype "passive"))
      (node (ref "VR103") (pin "CCW") (pinfunction "A_CCW") (pintype "passive"))
    )
    (net (code "37") (name "Net-(C118-1)") (class "Default")
      (node (ref "C118") (pin "P$1") (pinfunction "1_P$1") (pintype "passive"))
      (node (ref "VR103") (pin "CW") (pinfunction "E_CW") (pintype "passive"))
    )
    (net (code "38") (name "Net-(C118-2)") (class "Default")
      (node (ref "C118") (pin "P$2") (pinfunction "2_P$2") (pintype "passive"))
      (node (ref "R116") (pin "P$2") (pinfunction "2_P$2") (pintype "passive"))
    )
    (net (code "39") (name "Net-(C119-1)") (class "Default")
      (node (ref "C119") (pin "P$1") (pinfunction "1_P$1") (pintype "passive"))
      (node (ref "R113") (pin "P$1") (pinfunction "1_P$1") (pintype "passive"))
      (node (ref "R114") (pin "P$2") (pinfunction "2_P$2") (pintype "passive"))
      (node (ref "U101") (pin "2") (pinfunction "-IN_2") (pintype "input"))
    )
    (net (code "40") (name "Net-(C119-2)") (class "Default")
      (node (ref "C119") (pin "P$2") (pinfunction "2_P$2") (pintype "passive"))
      (node (ref "C120") (pin "POS") (pinfunction "+_POS") (pintype "passive"))
      (node (ref "R111") (pin "P$2") (pinfunction "2_P$2") (pintype "passive"))
      (node (ref "R115") (pin "P$2") (pinfunction "2_P$2") (pintype "passive"))
      (node (ref "U101") (pin "6") (pinfunction "OUT_6") (pintype "output"))
    )
    (net (code "41") (name "Net-(C120--)") (class "Default")
      (node (ref "C120") (pin "NEG") (pinfunction "-_NEG") (pintype "passive"))
      (node (ref "J105") (pin "1") (pinfunction "1_1") (pintype "passive"))
      (node (ref "J106") (pin "1") (pinfunction "1_1") (pintype "passive"))
    )
    (net (code "42") (name "Net-(C201-1)") (class "Default")
      (node (ref "C201") (pin "P$1") (pinfunction "1_P$1") (pintype "passive"))
      (node (ref "J201") (pin "2") (pinfunction "2_2") (pintype "passive"))
    )
    (net (code "43") (name "Net-(C201-2)") (class "Default")
      (node (ref "C201") (pin "P$2") (pinfunction "2_P$2") (pintype "passive"))
      (node (ref "C203") (pin "P$2") (pinfunction "2_P$2") (pintype "passive"))
      (node (ref "C204") (pin "P$1") (pinfunction "1_P$1") (pintype "passive"))
    )
    (net (code "44") (name "Net-(C202-1)") (class "Default")
      (node (ref "C202") (pin "P$1") (pinfunction "1_P$1") (pintype "passive"))
      (node (ref "J202") (pin "2") (pinfunction "2_2") (pintype "passive"))
    )
    (net (code "45") (name "Net-(C202-2)") (class "Default")
      (node (ref "C202") (pin "P$2") (pinfunction "2_P$2") (pintype "passive"))
      (node (ref "C205") (pin "P$2") (pinfunction "2_P$2") (pintype "passive"))
      (node (ref "C206") (pin "P$1") (pinfunction "1_P$1") (pintype "passive"))
    )
    (net (code "46") (name "Net-(C203-1)") (class "Default")
      (node (ref "C203") (pin "P$1") (pinfunction "1_P$1") (pintype "passive"))
      (node (ref "C207") (pin "POS") (pinfunction "+_POS") (pintype "passive"))
      (node (ref "J201") (pin "3") (pinfunction "3_3") (pintype "passive"))
      (node (ref "R201") (pin "P$1") (pinfunction "1_P$1") (pintype "passive"))
    )
    (net (code "47") (name "Net-(C204-2)") (class "Default")
      (node (ref "C204") (pin "P$2") (pinfunction "2_P$2") (pintype "passive"))
      (node (ref "C208") (pin "POS") (pinfunction "+_POS") (pintype "passive"))
      (node (ref "J201") (pin "1") (pinfunction "1_1") (pintype "passive"))
      (node (ref "R202") (pin "P$1") (pinfunction "1_P$1") (pintype "passive"))
    )
    (net (code "48") (name "Net-(C205-1)") (class "Default")
      (node (ref "C205") (pin "P$1") (pinfunction "1_P$1") (pintype "passive"))
      (node (ref "C209") (pin "POS") (pinfunction "+_POS") (pintype "passive"))
      (node (ref "J202") (pin "3") (pinfunction "3_3") (pintype "passive"))
    )
    (net (code "49") (name "Net-(C206-2)") (class "Default")
      (node (ref "C206") (pin "P$2") (pinfunction "2_P$2") (pintype "passive"))
      (node (ref "C210") (pin "POS") (pinfunction "+_POS") (pintype "passive"))
      (node (ref "J202") (pin "1") (pinfunction "1_1") (pintype "passive"))
    )
    (net (code "50") (name "Net-(C207--)") (class "Default")
      (node (ref "C207") (pin "NEG") (pinfunction "-_NEG") (pintype "passive"))
      (node (ref "R203") (pin "P$2") (pinfunction "2_P$2") (pintype "passive"))
    )
    (net (code "51") (name "Net-(C208--)") (class "Default")
      (node (ref "C208") (pin "NEG") (pinfunction "-_NEG") (pintype "passive"))
      (node (ref "R204") (pin "P$2") (pinfunction "2_P$2") (pintype "passive"))
    )
    (net (code "52") (name "Net-(C209--)") (class "Default")
      (node (ref "C209") (pin "NEG") (pinfunction "-_NEG") (pintype "passive"))
      (node (ref "R205") (pin "P$2") (pinfunction "2_P$2") (pintype "passive"))
    )
    (net (code "53") (name "Net-(C210--)") (class "Default")
      (node (ref "C210") (pin "NEG") (pinfunction "-_NEG") (pintype "passive"))
      (node (ref "R206") (pin "P$2") (pinfunction "2_P$2") (pintype "passive"))
    )
    (net (code "54") (name "Net-(C211-+)") (class "Default")
      (node (ref "C211") (pin "POS") (pinfunction "+_POS") (pintype "passive"))
      (node (ref "R210") (pin "P$2") (pinfunction "2_P$2") (pintype "passive"))
    )
    (net (code "55") (name "Net-(C211--)") (class "Default")
      (node (ref "C211") (pin "NEG") (pinfunction "-_NEG") (pintype "passive"))
      (node (ref "D203") (pin "A") (pinfunction "A_A") (pintype "passive"))
      (node (ref "IC201") (pin "8") (pinfunction "RG2_8") (pintype "bidirectional"))
    )
    (net (code "56") (name "Net-(C214-+)") (class "Default")
      (node (ref "C214") (pin "POS") (pinfunction "+_POS") (pintype "passive"))
      (node (ref "IC201") (pin "6") (pinfunction "OUT_6") (pintype "bidirectional"))
    )
    (net (code "57") (name "Net-(C214--)") (class "Default")
      (node (ref "C214") (pin "NEG") (pinfunction "-_NEG") (pintype "passive"))
      (node (ref "J204") (pin "1") (pinfunction "1_1") (pintype "passive"))
      (node (ref "R212") (pin "P$1") (pinfunction "1_P$1") (pintype "passive"))
      (node (ref "R216") (pin "P$1") (pinfunction "1_P$1") (pintype "passive"))
    )
    (net (code "58") (name "Net-(C215-1)") (class "Default")
      (node (ref "C215") (pin "P$1") (pinfunction "1_P$1") (pintype "passive"))
      (node (ref "R211") (pin "P$1") (pinfunction "1_P$1") (pintype "passive"))
      (node (ref "VR202") (pin "CCW") (pinfunction "A_CCW") (pintype "passive"))
    )
    (net (code "59") (name "Net-(C215-2)") (class "Default")
      (node (ref "C215") (pin "P$2") (pinfunction "2_P$2") (pintype "passive"))
      (node (ref "C216") (pin "P$2") (pinfunction "2_P$2") (pintype "passive"))
      (node (ref "R213") (pin "P$2") (pinfunction "2_P$2") (pintype "passive"))
      (node (ref "VR202") (pin "WIP") (pinfunction "S_WIP") (pintype "passive"))
    )
    (net (code "60") (name "Net-(C216-1)") (class "Default")
      (node (ref "C216") (pin "P$1") (pinfunction "1_P$1") (pintype "passive"))
      (node (ref "R212") (pin "P$2") (pinfunction "2_P$2") (pintype "passive"))
      (node (ref "VR202") (pin "CW") (pinfunction "E_CW") (pintype "passive"))
    )
    (net (code "61") (name "Net-(C217-1)") (class "Default")
      (node (ref "C217") (pin "P$1") (pinfunction "1_P$1") (pintype "passive"))
      (node (ref "R215") (pin "P$1") (pinfunction "1_P$1") (pintype "passive"))
    )
    (net (code "62") (name "Net-(C217-2)") (class "Default")
      (node (ref "C217") (pin "P$2") (pinfunction "2_P$2") (pintype "passive"))
      (node (ref "VR203") (pin "CCW") (pinfunction "A_CCW") (pintype "passive"))
    )
    (net (code "63") (name "Net-(C218-1)") (class "Default")
      (node (ref "C218") (pin "P$1") (pinfunction "1_P$1") (pintype "passive"))
      (node (ref "VR203") (pin "CW") (pinfunction "E_CW") (pintype "passive"))
    )
    (net (code "64") (name "Net-(C218-2)") (class "Default")
      (node (ref "C218") (pin "P$2") (pinfunction "2_P$2") (pintype "passive"))
      (node (ref "R216") (pin "P$2") (pinfunction "2_P$2") (pintype "passive"))
    )
    (net (code "65") (name "Net-(C219-1)") (class "Default")
      (node (ref "C219") (pin "P$1") (pinfunction "1_P$1") (pintype "passive"))
      (node (ref "R213") (pin "P$1") (pinfunction "1_P$1") (pintype "passive"))
      (node (ref "R214") (pin "P$2") (pinfunction "2_P$2") (pintype "passive"))
      (node (ref "U201") (pin "2") (pinfunction "-IN_2") (pintype "input"))
    )
    (net (code "66") (name "Net-(C219-2)") (class "Default")
      (node (ref "C219") (pin "P$2") (pinfunction "2_P$2") (pintype "passive"))
      (node (ref "C220") (pin "POS") (pinfunction "+_POS") (pintype "passive"))
      (node (ref "R211") (pin "P$2") (pinfunction "2_P$2") (pintype "passive"))
      (node (ref "R215") (pin "P$2") (pinfunction "2_P$2") (pintype "passive"))
      (node (ref "U201") (pin "6") (pinfunction "OUT_6") (pintype "output"))
    )
    (net (code "67") (name "Net-(C220--)") (class "Default")
      (node (ref "C220") (pin "NEG") (pinfunction "-_NEG") (pintype "passive"))
      (node (ref "J205") (pin "1") (pinfunction "1_1") (pintype "passive"))
      (node (ref "J206") (pin "1") (pinfunction "1_1") (pintype "passive"))
    )
    (net (code "68") (name "Net-(C301-1)") (class "Default")
      (node (ref "C301") (pin "P$1") (pinfunction "1_P$1") (pintype "passive"))
      (node (ref "J301") (pin "2") (pinfunction "2_2") (pintype "passive"))
    )
    (net (code "69") (name "Net-(C301-2)") (class "Default")
      (node (ref "C301") (pin "P$2") (pinfunction "2_P$2") (pintype "passive"))
      (node (ref "C303") (pin "P$2") (pinfunction "2_P$2") (pintype "passive"))
      (node (ref "C304") (pin "P$1") (pinfunction "1_P$1") (pintype "passive"))
    )
    (net (code "70") (name "Net-(C302-1)") (class "Default")
      (node (ref "C302") (pin "P$1") (pinfunction "1_P$1") (pintype "passive"))
      (node (ref "J302") (pin "2") (pinfunction "2_2") (pintype "passive"))
    )
    (net (code "71") (name "Net-(C302-2)") (class "Default")
      (node (ref "C302") (pin "P$2") (pinfunction "2_P$2") (pintype "passive"))
      (node (ref "C305") (pin "P$2") (pinfunction "2_P$2") (pintype "passive"))
      (node (ref "C306") (pin "P$1") (pinfunction "1_P$1") (pintype "passive"))
    )
    (net (code "72") (name "Net-(C303-1)") (class "Default")
      (node (ref "C303") (pin "P$1") (pinfunction "1_P$1") (pintype "passive"))
      (node (ref "C307") (pin "POS") (pinfunction "+_POS") (pintype "passive"))
      (node (ref "J301") (pin "3") (pinfunction "3_3") (pintype "passive"))
      (node (ref "R301") (pin "P$1") (pinfunction "1_P$1") (pintype "passive"))
    )
    (net (code "73") (name "Net-(C304-2)") (class "Default")
      (node (ref "C304") (pin "P$2") (pinfunction "2_P$2") (pintype "passive"))
      (node (ref "C308") (pin "POS") (pinfunction "+_POS") (pintype "passive"))
      (node (ref "J301") (pin "1") (pinfunction "1_1") (pintype "passive"))
      (node (ref "R302") (pin "P$1") (pinfunction "1_P$1") (pintype "passive"))
    )
    (net (code "74") (name "Net-(C305-1)") (class "Default")
      (node (ref "C305") (pin "P$1") (pinfunction "1_P$1") (pintype "passive"))
      (node (ref "C309") (pin "POS") (pinfunction "+_POS") (pintype "passive"))
      (node (ref "J302") (pin "3") (pinfunction "3_3") (pintype "passive"))
    )
    (net (code "75") (name "Net-(C306-2)") (class "Default")
      (node (ref "C306") (pin "P$2") (pinfunction "2_P$2") (pintype "passive"))
      (node (ref "C310") (pin "POS") (pinfunction "+_POS") (pintype "passive"))
      (node (ref "J302") (pin "1") (pinfunction "1_1") (pintype "passive"))
    )
    (net (code "76") (name "Net-(C307--)") (class "Default")
      (node (ref "C307") (pin "NEG") (pinfunction "-_NEG") (pintype "passive"))
      (node (ref "R303") (pin "P$2") (pinfunction "2_P$2") (pintype "passive"))
    )
    (net (code "77") (name "Net-(C308--)") (class "Default")
      (node (ref "C308") (pin "NEG") (pinfunction "-_NEG") (pintype "passive"))
      (node (ref "R304") (pin "P$2") (pinfunction "2_P$2") (pintype "passive"))
    )
    (net (code "78") (name "Net-(C309--)") (class "Default")
      (node (ref "C309") (pin "NEG") (pinfunction "-_NEG") (pintype "passive"))
      (node (ref "R305") (pin "P$2") (pinfunction "2_P$2") (pintype "passive"))
    )
    (net (code "79") (name "Net-(C310--)") (class "Default")
      (node (ref "C310") (pin "NEG") (pinfunction "-_NEG") (pintype "passive"))
      (node (ref "R306") (pin "P$2") (pinfunction "2_P$2") (pintype "passive"))
    )
    (net (code "80") (name "Net-(C311-+)") (class "Default")
      (node (ref "C311") (pin "POS") (pinfunction "+_POS") (pintype "passive"))
      (node (ref "R310") (pin "P$2") (pinfunction "2_P$2") (pintype "passive"))
    )
    (net (code "81") (name "Net-(C311--)") (class "Default")
      (node (ref "C311") (pin "NEG") (pinfunction "-_NEG") (pintype "passive"))
      (node (ref "D303") (pin "A") (pinfunction "A_A") (pintype "passive"))
      (node (ref "IC301") (pin "8") (pinfunction "RG2_8") (pintype "bidirectional"))
    )
    (net (code "82") (name "Net-(C314-+)") (class "Default")
      (node (ref "C314") (pin "POS") (pinfunction "+_POS") (pintype "passive"))
      (node (ref "IC301") (pin "6") (pinfunction "OUT_6") (pintype "bidirectional"))
    )
    (net (code "83") (name "Net-(C314--)") (class "Default")
      (node (ref "C314") (pin "NEG") (pinfunction "-_NEG") (pintype "passive"))
      (node (ref "J304") (pin "1") (pinfunction "1_1") (pintype "passive"))
      (node (ref "R312") (pin "P$1") (pinfunction "1_P$1") (pintype "passive"))
      (node (ref "R316") (pin "P$1") (pinfunction "1_P$1") (pintype "passive"))
    )
    (net (code "84") (name "Net-(C315-1)") (class "Default")
      (node (ref "C315") (pin "P$1") (pinfunction "1_P$1") (pintype "passive"))
      (node (ref "R311") (pin "P$1") (pinfunction "1_P$1") (pintype "passive"))
      (node (ref "VR302") (pin "CCW") (pinfunction "A_CCW") (pintype "passive"))
    )
    (net (code "85") (name "Net-(C315-2)") (class "Default")
      (node (ref "C315") (pin "P$2") (pinfunction "2_P$2") (pintype "passive"))
      (node (ref "C316") (pin "P$2") (pinfunction "2_P$2") (pintype "passive"))
      (node (ref "R313") (pin "P$2") (pinfunction "2_P$2") (pintype "passive"))
      (node (ref "VR302") (pin "WIP") (pinfunction "S_WIP") (pintype "passive"))
    )
    (net (code "86") (name "Net-(C316-1)") (class "Default")
      (node (ref "C316") (pin "P$1") (pinfunction "1_P$1") (pintype "passive"))
      (node (ref "R312") (pin "P$2") (pinfunction "2_P$2") (pintype "passive"))
      (node (ref "VR302") (pin "CW") (pinfunction "E_CW") (pintype "passive"))
    )
    (net (code "87") (name "Net-(C317-1)") (class "Default")
      (node (ref "C317") (pin "P$1") (pinfunction "1_P$1") (pintype "passive"))
      (node (ref "R315") (pin "P$1") (pinfunction "1_P$1") (pintype "passive"))
    )
    (net (code "88") (name "Net-(C317-2)") (class "Default")
      (node (ref "C317") (pin "P$2") (pinfunction "2_P$2") (pintype "passive"))
      (node (ref "VR303") (pin "CCW") (pinfunction "A_CCW") (pintype "passive"))
    )
    (net (code "89") (name "Net-(C318-1)") (class "Default")
      (node (ref "C318") (pin "P$1") (pinfunction "1_P$1") (pintype "passive"))
      (node (ref "VR303") (pin "CW") (pinfunction "E_CW") (pintype "passive"))
    )
    (net (code "90") (name "Net-(C318-2)") (class "Default")
      (node (ref "C318") (pin "P$2") (pinfunction "2_P$2") (pintype "passive"))
      (node (ref "R316") (pin "P$2") (pinfunction "2_P$2") (pintype "passive"))
    )
    (net (code "91") (name "Net-(C319-1)") (class "Default")
      (node (ref "C319") (pin "P$1") (pinfunction "1_P$1") (pintype "passive"))
      (node (ref "R313") (pin "P$1") (pinfunction "1_P$1") (pintype "passive"))
      (node (ref "R314") (pin "P$2") (pinfunction "2_P$2") (pintype "passive"))
      (node (ref "U301") (pin "2") (pinfunction "-IN_2") (pintype "input"))
    )
    (net (code "92") (name "Net-(C319-2)") (class "Default")
      (node (ref "C319") (pin "P$2") (pinfunction "2_P$2") (pintype "passive"))
      (node (ref "C320") (pin "POS") (pinfunction "+_POS") (pintype "passive"))
      (node (ref "R311") (pin "P$2") (pinfunction "2_P$2") (pintype "passive"))
      (node (ref "R315") (pin "P$2") (pinfunction "2_P$2") (pintype "passive"))
      (node (ref "U301") (pin "6") (pinfunction "OUT_6") (pintype "output"))
    )
    (net (code "93") (name "Net-(C320--)") (class "Default")
      (node (ref "C320") (pin "NEG") (pinfunction "-_NEG") (pintype "passive"))
      (node (ref "J305") (pin "1") (pinfunction "1_1") (pintype "passive"))
      (node (ref "J306") (pin "1") (pinfunction "1_1") (pintype "passive"))
    )
    (net (code "94") (name "Net-(C401-1)") (class "Default")
      (node (ref "C401") (pin "P$1") (pinfunction "1_P$1") (pintype "passive"))
      (node (ref "J401") (pin "2") (pinfunction "2_2") (pintype "passive"))
    )
    (net (code "95") (name "Net-(C401-2)") (class "Default")
      (node (ref "C401") (pin "P$2") (pinfunction "2_P$2") (pintype "passive"))
      (node (ref "C403") (pin "P$2") (pinfunction "2_P$2") (pintype "passive"))
      (node (ref "C404") (pin "P$1") (pinfunction "1_P$1") (pintype "passive"))
    )
    (net (code "96") (name "Net-(C402-1)") (class "Default")
      (node (ref "C402") (pin "P$1") (pinfunction "1_P$1") (pintype "passive"))
      (node (ref "J402") (pin "2") (pinfunction "2_2") (pintype "passive"))
    )
    (net (code "97") (name "Net-(C402-2)") (class "Default")
      (node (ref "C402") (pin "P$2") (pinfunction "2_P$2") (pintype "passive"))
      (node (ref "C405") (pin "P$2") (pinfunction "2_P$2") (pintype "passive"))
      (node (ref "C406") (pin "P$1") (pinfunction "1_P$1") (pintype "passive"))
    )
    (net (code "98") (name "Net-(C403-1)") (class "Default")
      (node (ref "C403") (pin "P$1") (pinfunction "1_P$1") (pintype "passive"))
      (node (ref "C407") (pin "POS") (pinfunction "+_POS") (pintype "passive"))
      (node (ref "J401") (pin "3") (pinfunction "3_3") (pintype "passive"))
      (node (ref "R401") (pin "P$1") (pinfunction "1_P$1") (pintype "passive"))
    )
    (net (code "99") (name "Net-(C404-2)") (class "Default")
      (node (ref "C404") (pin "P$2") (pinfunction "2_P$2") (pintype "passive"))
      (node (ref "C408") (pin "POS") (pinfunction "+_POS") (pintype "passive"))
      (node (ref "J401") (pin "1") (pinfunction "1_1") (pintype "passive"))
      (node (ref "R402") (pin "P$1") (pinfunction "1_P$1") (pintype "passive"))
    )
    (net (code "100") (name "Net-(C405-1)") (class "Default")
      (node (ref "C405") (pin "P$1") (pinfunction "1_P$1") (pintype "passive"))
      (node (ref "C409") (pin "POS") (pinfunction "+_POS") (pintype "passive"))
      (node (ref "J402") (pin "3") (pinfunction "3_3") (pintype "passive"))
    )
    (net (code "101") (name "Net-(C406-2)") (class "Default")
      (node (ref "C406") (pin "P$2") (pinfunction "2_P$2") (pintype "passive"))
      (node (ref "C410") (pin "POS") (pinfunction "+_POS") (pintype "passive"))
      (node (ref "J402") (pin "1") (pinfunction "1_1") (pintype "passive"))
    )
    (net (code "102") (name "Net-(C407--)") (class "Default")
      (node (ref "C407") (pin "NEG") (pinfunction "-_NEG") (pintype "passive"))
      (node (ref "R403") (pin "P$2") (pinfunction "2_P$2") (pintype "passive"))
    )
    (net (code "103") (name "Net-(C408--)") (class "Default")
      (node (ref "C408") (pin "NEG") (pinfunction "-_NEG") (pintype "passive"))
      (node (ref "R404") (pin "P$2") (pinfunction "2_P$2") (pintype "passive"))
    )
    (net (code "104") (name "Net-(C409--)") (class "Default")
      (node (ref "C409") (pin "NEG") (pinfunction "-_NEG") (pintype "passive"))
      (node (ref "R405") (pin "P$2") (pinfunction "2_P$2") (pintype "passive"))
    )
    (net (code "105") (name "Net-(C410--)") (class "Default")
      (node (ref "C410") (pin "NEG") (pinfunction "-_NEG") (pintype "passive"))
      (node (ref "R406") (pin "P$2") (pinfunction "2_P$2") (pintype "passive"))
    )
    (net (code "106") (name "Net-(C411-+)") (class "Default")
      (node (ref "C411") (pin "POS") (pinfunction "+_POS") (pintype "passive"))
      (node (ref "R410") (pin "P$2") (pinfunction "2_P$2") (pintype "passive"))
    )
    (net (code "107") (name "Net-(C411--)") (class "Default")
      (node (ref "C411") (pin "NEG") (pinfunction "-_NEG") (pintype "passive"))
      (node (ref "D403") (pin "A") (pinfunction "A_A") (pintype "passive"))
      (node (ref "IC401") (pin "8") (pinfunction "RG2_8") (pintype "bidirectional"))
    )
    (net (code "108") (name "Net-(C414-+)") (class "Default")
      (node (ref "C414") (pin "POS") (pinfunction "+_POS") (pintype "passive"))
      (node (ref "IC401") (pin "6") (pinfunction "OUT_6") (pintype "bidirectional"))
    )
    (net (code "109") (name "Net-(C414--)") (class "Default")
      (node (ref "C414") (pin "NEG") (pinfunction "-_NEG") (pintype "passive"))
      (node (ref "J404") (pin "1") (pinfunction "1_1") (pintype "passive"))
      (node (ref "R412") (pin "P$1") (pinfunction "1_P$1") (pintype "passive"))
      (node (ref "R416") (pin "P$1") (pinfunction "1_P$1") (pintype "passive"))
    )
    (net (code "110") (name "Net-(C415-1)") (class "Default")
      (node (ref "C415") (pin "P$1") (pinfunction "1_P$1") (pintype "passive"))
      (node (ref "R411") (pin "P$1") (pinfunction "1_P$1") (pintype "passive"))
      (node (ref "VR402") (pin "CCW") (pinfunction "A_CCW") (pintype "passive"))
    )
    (net (code "111") (name "Net-(C415-2)") (class "Default")
      (node (ref "C415") (pin "P$2") (pinfunction "2_P$2") (pintype "passive"))
      (node (ref "C416") (pin "P$2") (pinfunction "2_P$2") (pintype "passive"))
      (node (ref "R413") (pin "P$2") (pinfunction "2_P$2") (pintype "passive"))
      (node (ref "VR402") (pin "WIP") (pinfunction "S_WIP") (pintype "passive"))
    )
    (net (code "112") (name "Net-(C416-1)") (class "Default")
      (node (ref "C416") (pin "P$1") (pinfunction "1_P$1") (pintype "passive"))
      (node (ref "R412") (pin "P$2") (pinfunction "2_P$2") (pintype "passive"))
      (node (ref "VR402") (pin "CW") (pinfunction "E_CW") (pintype "passive"))
    )
    (net (code "113") (name "Net-(C417-1)") (class "Default")
      (node (ref "C417") (pin "P$1") (pinfunction "1_P$1") (pintype "passive"))
      (node (ref "R415") (pin "P$1") (pinfunction "1_P$1") (pintype "passive"))
    )
    (net (code "114") (name "Net-(C417-2)") (class "Default")
      (node (ref "C417") (pin "P$2") (pinfunction "2_P$2") (pintype "passive"))
      (node (ref "VR403") (pin "CCW") (pinfunction "A_CCW") (pintype "passive"))
    )
    (net (code "115") (name "Net-(C418-1)") (class "Default")
      (node (ref "C418") (pin "P$1") (pinfunction "1_P$1") (pintype "passive"))
      (node (ref "VR403") (pin "CW") (pinfunction "E_CW") (pintype "passive"))
    )
    (net (code "116") (name "Net-(C418-2)") (class "Default")
      (node (ref "C418") (pin "P$2") (pinfunction "2_P$2") (pintype "passive"))
      (node (ref "R416") (pin "P$2") (pinfunction "2_P$2") (pintype "passive"))
    )
    (net (code "117") (name "Net-(C419-1)") (class "Default")
      (node (ref "C419") (pin "P$1") (pinfunction "1_P$1") (pintype "passive"))
      (node (ref "R413") (pin "P$1") (pinfunction "1_P$1") (pintype "passive"))
      (node (ref "R414") (pin "P$2") (pinfunction "2_P$2") (pintype "passive"))
      (node (ref "U401") (pin "2") (pinfunction "-IN_2") (pintype "input"))
    )
    (net (code "118") (name "Net-(C419-2)") (class "Default")
      (node (ref "C419") (pin "P$2") (pinfunction "2_P$2") (pintype "passive"))
      (node (ref "C420") (pin "POS") (pinfunction "+_POS") (pintype "passive"))
      (node (ref "R411") (pin "P$2") (pinfunction "2_P$2") (pintype "passive"))
      (node (ref "R415") (pin "P$2") (pinfunction "2_P$2") (pintype "passive"))
      (node (ref "U401") (pin "6") (pinfunction "OUT_6") (pintype "output"))
    )
    (net (code "119") (name "Net-(C420--)") (class "Default")
      (node (ref "C420") (pin "NEG") (pinfunction "-_NEG") (pintype "passive"))
      (node (ref "J405") (pin "1") (pinfunction "1_1") (pintype "passive"))
      (node (ref "J406") (pin "1") (pinfunction "1_1") (pintype "passive"))
    )
    (net (code "120") (name "Net-(C501-1)") (class "Default")
      (node (ref "C501") (pin "P$1") (pinfunction "1_P$1") (pintype "passive"))
      (node (ref "R501") (pin "P$1") (pinfunction "1_P$1") (pintype "passive"))
      (node (ref "R502") (pin "P$1") (pinfunction "1_P$1") (pintype "passive"))
      (node (ref "R503") (pin "P$1") (pinfunction "1_P$1") (pintype "passive"))
      (node (ref "R504") (pin "P$1") (pinfunction "1_P$1") (pintype "passive"))
      (node (ref "R506") (pin "P$2") (pinfunction "2_P$2") (pintype "passive"))
      (node (ref "U501") (pin "2") (pinfunction "-IN_2") (pintype "input"))
    )
    (net (code "121") (name "Net-(C501-2)") (class "Default")
      (node (ref "C501") (pin "P$2") (pinfunction "2_P$2") (pintype "passive"))
      (node (ref "R507") (pin "P$2") (pinfunction "2_P$2") (pintype "passive"))
      (node (ref "U501") (pin "6") (pinfunction "OUT_6") (pintype "output"))
    )
    (net (code "122") (name "Net-(C502-+)") (class "Default")
      (node (ref "C502") (pin "POS") (pinfunction "+_POS") (pintype "passive"))
      (node (ref "R506") (pin "P$1") (pinfunction "1_P$1") (pintype "passive"))
      (node (ref "R507") (pin "P$1") (pinfunction "1_P$1") (pintype "passive"))
    )
    (net (code "123") (name "Net-(C505-1)") (class "Default")
      (node (ref "C505") (pin "P$1") (pinfunction "1_P$1") (pintype "passive"))
      (node (ref "FB501") (pin "P$2") (pinfunction "2_P$2") (pintype "passive"))
      (node (ref "J501") (pin "1") (pinfunction "1_1") (pintype "passive"))
    )
    (net (code "124") (name "Net-(C601-1)") (class "Default")
      (node (ref "C601") (pin "P$1") (pinfunction "1_P$1") (pintype "passive"))
      (node (ref "R601") (pin "P$1") (pinfunction "1_P$1") (pintype "passive"))
      (node (ref "R602") (pin "P$1") (pinfunction "1_P$1") (pintype "passive"))
      (node (ref "R603") (pin "P$1") (pinfunction "1_P$1") (pintype "passive"))
      (node (ref "R604") (pin "P$1") (pinfunction "1_P$1") (pintype "passive"))
      (node (ref "R606") (pin "P$2") (pinfunction "2_P$2") (pintype "passive"))
      (node (ref "U601") (pin "2") (pinfunction "-IN_2") (pintype "input"))
    )
    (net (code "125") (name "Net-(C601-2)") (class "Default")
      (node (ref "C601") (pin "P$2") (pinfunction "2_P$2") (pintype "passive"))
      (node (ref "R607") (pin "P$2") (pinfunction "2_P$2") (pintype "passive"))
      (node (ref "U601") (pin "6") (pinfunction "OUT_6") (pintype "output"))
    )
    (net (code "126") (name "Net-(C602-+)") (class "Default")
      (node (ref "C602") (pin "POS") (pinfunction "+_POS") (pintype "passive"))
      (node (ref "R606") (pin "P$1") (pinfunction "1_P$1") (pintype "passive"))
      (node (ref "R607") (pin "P$1") (pinfunction "1_P$1") (pintype "passive"))
    )
    (net (code "127") (name "Net-(C605-1)") (class "Default")
      (node (ref "C605") (pin "P$1") (pinfunction "1_P$1") (pintype "passive"))
      (node (ref "FB601") (pin "P$2") (pinfunction "2_P$2") (pintype "passive"))
      (node (ref "J601") (pin "1") (pinfunction "1_1") (pintype "passive"))
    )
    (net (code "128") (name "Net-(D101-~)") (class "Default")
      (node (ref "D101") (pin "AC1") (pinfunction "~_AC1") (pintype "bidirectional"))
      (node (ref "D103") (pin "C") (pinfunction "C_C") (pintype "passive"))
      (node (ref "IC101") (pin "3") (pinfunction "+IN_3") (pintype "bidirectional"))
      (node (ref "R104") (pin "P$1") (pinfunction "1_P$1") (pintype "passive"))
      (node (ref "R106") (pin "P$1") (pinfunction "1_P$1") (pintype "passive"))
      (node (ref "R109") (pin "P$2") (pinfunction "2_P$2") (pintype "passive"))
    )
    (net (code "129") (name "Net-(D101-~{2})") (class "Default")
      (node (ref "D101") (pin "AC2") (pinfunction "~{2}_AC2") (pintype "bidirectional"))
      (node (ref "D102") (pin "C") (pinfunction "C_C") (pintype "passive"))
      (node (ref "IC101") (pin "2") (pinfunction "-IN_2") (pintype "bidirectional"))
      (node (ref "R103") (pin "P$1") (pinfunction "1_P$1") (pintype "passive"))
      (node (ref "R105") (pin "P$1") (pinfunction "1_P$1") (pintype "passive"))
      (node (ref "R108") (pin "P$1") (pinfunction "1_P$1") (pintype "passive"))
    )
    (net (code "130") (name "Net-(D201-~)") (class "Default")
      (node (ref "D201") (pin "AC1") (pinfunction "~_AC1") (pintype "bidirectional"))
      (node (ref "D203") (pin "C") (pinfunction "C_C") (pintype "passive"))
      (node (ref "IC201") (pin "3") (pinfunction "+IN_3") (pintype "bidirectional"))
      (node (ref "R204") (pin "P$1") (pinfunction "1_P$1") (pintype "passive"))
      (node (ref "R206") (pin "P$1") (pinfunction "1_P$1") (pintype "passive"))
      (node (ref "R209") (pin "P$2") (pinfunction "2_P$2") (pintype "passive"))
    )
    (net (code "131") (name "Net-(D201-~{2})") (class "Default")
      (node (ref "D201") (pin "AC2") (pinfunction "~{2}_AC2") (pintype "bidirectional"))
      (node (ref "D202") (pin "C") (pinfunction "C_C") (pintype "passive"))
      (node (ref "IC201") (pin "2") (pinfunction "-IN_2") (pintype "bidirectional"))
      (node (ref "R203") (pin "P$1") (pinfunction "1_P$1") (pintype "passive"))
      (node (ref "R205") (pin "P$1") (pinfunction "1_P$1") (pintype "passive"))
      (node (ref "R208") (pin "P$1") (pinfunction "1_P$1") (pintype "passive"))
    )
    (net (code "132") (name "Net-(D301-~)") (class "Default")
      (node (ref "D301") (pin "AC1") (pinfunction "~_AC1") (pintype "bidirectional"))
      (node (ref "D303") (pin "C") (pinfunction "C_C") (pintype "passive"))
      (node (ref "IC301") (pin "3") (pinfunction "+IN_3") (pintype "bidirectional"))
      (node (ref "R304") (pin "P$1") (pinfunction "1_P$1") (pintype "passive"))
      (node (ref "R306") (pin "P$1") (pinfunction "1_P$1") (pintype "passive"))
      (node (ref "R309") (pin "P$2") (pinfunction "2_P$2") (pintype "passive"))
    )
    (net (code "133") (name "Net-(D301-~{2})") (class "Default")
      (node (ref "D301") (pin "AC2") (pinfunction "~{2}_AC2") (pintype "bidirectional"))
      (node (ref "D302") (pin "C") (pinfunction "C_C") (pintype "passive"))
      (node (ref "IC301") (pin "2") (pinfunction "-IN_2") (pintype "bidirectional"))
      (node (ref "R303") (pin "P$1") (pinfunction "1_P$1") (pintype "passive"))
      (node (ref "R305") (pin "P$1") (pinfunction "1_P$1") (pintype "passive"))
      (node (ref "R308") (pin "P$1") (pinfunction "1_P$1") (pintype "passive"))
    )
    (net (code "134") (name "Net-(D401-~)") (class "Default")
      (node (ref "D401") (pin "AC1") (pinfunction "~_AC1") (pintype "bidirectional"))
      (node (ref "D403") (pin "C") (pinfunction "C_C") (pintype "passive"))
      (node (ref "IC401") (pin "3") (pinfunction "+IN_3") (pintype "bidirectional"))
      (node (ref "R404") (pin "P$1") (pinfunction "1_P$1") (pintype "passive"))
      (node (ref "R406") (pin "P$1") (pinfunction "1_P$1") (pintype "passive"))
      (node (ref "R409") (pin "P$2") (pinfunction "2_P$2") (pintype "passive"))
    )
    (net (code "135") (name "Net-(D401-~{2})") (class "Default")
      (node (ref "D401") (pin "AC2") (pinfunction "~{2}_AC2") (pintype "bidirectional"))
      (node (ref "D402") (pin "C") (pinfunction "C_C") (pintype "passive"))
      (node (ref "IC401") (pin "2") (pinfunction "-IN_2") (pintype "bidirectional"))
      (node (ref "R403") (pin "P$1") (pinfunction "1_P$1") (pintype "passive"))
      (node (ref "R405") (pin "P$1") (pinfunction "1_P$1") (pintype "passive"))
      (node (ref "R408") (pin "P$1") (pinfunction "1_P$1") (pintype "passive"))
    )
    (net (code "136") (name "Net-(D502-C)") (class "Default")
      (node (ref "D502") (pin "20") (pinfunction "C_20") (pintype "passive"))
      (node (ref "U502") (pin "10") (pinfunction "LED10_10") (pintype "output"))
    )
    (net (code "137") (name "Net-(D502-C1)") (class "Default")
      (node (ref "D502") (pin "19") (pinfunction "C1_19") (pintype "passive"))
      (node (ref "U502") (pin "11") (pinfunction "LED9_11") (pintype "output"))
    )
    (net (code "138") (name "Net-(D502-C2)") (class "Default")
      (node (ref "D502") (pin "18") (pinfunction "C2_18") (pintype "passive"))
      (node (ref "U502") (pin "12") (pinfunction "LED8_12") (pintype "output"))
    )
    (net (code "139") (name "Net-(D502-C3)") (class "Default")
      (node (ref "D502") (pin "17") (pinfunction "C3_17") (pintype "passive"))
      (node (ref "U502") (pin "13") (pinfunction "LED7_13") (pintype "output"))
    )
    (net (code "140") (name "Net-(D502-C4)") (class "Default")
      (node (ref "D502") (pin "16") (pinfunction "C4_16") (pintype "passive"))
      (node (ref "U502") (pin "14") (pinfunction "LED6_14") (pintype "output"))
    )
    (net (code "141") (name "Net-(D502-C5)") (class "Default")
      (node (ref "D502") (pin "15") (pinfunction "C5_15") (pintype "passive"))
      (node (ref "U502") (pin "15") (pinfunction "LED5_15") (pintype "output"))
    )
    (net (code "142") (name "Net-(D502-C6)") (class "Default")
      (node (ref "D502") (pin "14") (pinfunction "C6_14") (pintype "passive"))
      (node (ref "U502") (pin "16") (pinfunction "LED4_16") (pintype "output"))
    )
    (net (code "143") (name "Net-(D502-C7)") (class "Default")
      (node (ref "D502") (pin "13") (pinfunction "C7_13") (pintype "passive"))
      (node (ref "U502") (pin "17") (pinfunction "LED3_17") (pintype "output"))
    )
    (net (code "144") (name "Net-(D502-C8)") (class "Default")
      (node (ref "D502") (pin "12") (pinfunction "C8_12") (pintype "passive"))
      (node (ref "U502") (pin "18") (pinfunction "LED2_18") (pintype "output"))
    )
    (net (code "145") (name "Net-(D502-C9)") (class "Default")
      (node (ref "D502") (pin "11") (pinfunction "C9_11") (pintype "passive"))
      (node (ref "U502") (pin "1") (pinfunction "LED1_1") (pintype "output"))
    )
    (net (code "146") (name "Net-(D602-C)") (class "Default")
      (node (ref "D602") (pin "20") (pinfunction "C_20") (pintype "passive"))
      (node (ref "U602") (pin "10") (pinfunction "LED10_10") (pintype "output"))
    )
    (net (code "147") (name "Net-(D602-C1)") (class "Default")
      (node (ref "D602") (pin "19") (pinfunction "C1_19") (pintype "passive"))
      (node (ref "U602") (pin "11") (pinfunction "LED9_11") (pintype "output"))
    )
    (net (code "148") (name "Net-(D602-C2)") (class "Default")
      (node (ref "D602") (pin "18") (pinfunction "C2_18") (pintype "passive"))
      (node (ref "U602") (pin "12") (pinfunction "LED8_12") (pintype "output"))
    )
    (net (code "149") (name "Net-(D602-C3)") (class "Default")
      (node (ref "D602") (pin "17") (pinfunction "C3_17") (pintype "passive"))
      (node (ref "U602") (pin "13") (pinfunction "LED7_13") (pintype "output"))
    )
    (net (code "150") (name "Net-(D602-C4)") (class "Default")
      (node (ref "D602") (pin "16") (pinfunction "C4_16") (pintype "passive"))
      (node (ref "U602") (pin "14") (pinfunction "LED6_14") (pintype "output"))
    )
    (net (code "151") (name "Net-(D602-C5)") (class "Default")
      (node (ref "D602") (pin "15") (pinfunction "C5_15") (pintype "passive"))
      (node (ref "U602") (pin "15") (pinfunction "LED5_15") (pintype "output"))
    )
    (net (code "152") (name "Net-(D602-C6)") (class "Default")
      (node (ref "D602") (pin "14") (pinfunction "C6_14") (pintype "passive"))
      (node (ref "U602") (pin "16") (pinfunction "LED4_16") (pintype "output"))
    )
    (net (code "153") (name "Net-(D602-C7)") (class "Default")
      (node (ref "D602") (pin "13") (pinfunction "C7_13") (pintype "passive"))
      (node (ref "U602") (pin "17") (pinfunction "LED3_17") (pintype "output"))
    )
    (net (code "154") (name "Net-(D602-C8)") (class "Default")
      (node (ref "D602") (pin "12") (pinfunction "C8_12") (pintype "passive"))
      (node (ref "U602") (pin "18") (pinfunction "LED2_18") (pintype "output"))
    )
    (net (code "155") (name "Net-(D602-C9)") (class "Default")
      (node (ref "D602") (pin "11") (pinfunction "C9_11") (pintype "passive"))
      (node (ref "U602") (pin "1") (pinfunction "LED1_1") (pintype "output"))
    )
    (net (code "156") (name "Net-(IC101-RG1)") (class "Default")
      (node (ref "D102") (pin "A") (pinfunction "A_A") (pintype "passive"))
      (node (ref "IC101") (pin "1") (pinfunction "RG1_1") (pintype "bidirectional"))
      (node (ref "VR101") (pin "CCW") (pinfunction "A_CCW") (pintype "passive"))
      (node (ref "VR101") (pin "WIP") (pinfunction "S_WIP") (pintype "passive"))
    )
    (net (code "157") (name "Net-(IC201-RG1)") (class "Default")
      (node (ref "D202") (pin "A") (pinfunction "A_A") (pintype "passive"))
      (node (ref "IC201") (pin "1") (pinfunction "RG1_1") (pintype "bidirectional"))
      (node (ref "VR201") (pin "CCW") (pinfunction "A_CCW") (pintype "passive"))
      (node (ref "VR201") (pin "WIP") (pinfunction "S_WIP") (pintype "passive"))
    )
    (net (code "158") (name "Net-(IC301-RG1)") (class "Default")
      (node (ref "D302") (pin "A") (pinfunction "A_A") (pintype "passive"))
      (node (ref "IC301") (pin "1") (pinfunction "RG1_1") (pintype "bidirectional"))
      (node (ref "VR301") (pin "CCW") (pinfunction "A_CCW") (pintype "passive"))
      (node (ref "VR301") (pin "WIP") (pinfunction "S_WIP") (pintype "passive"))
    )
    (net (code "159") (name "Net-(IC401-RG1)") (class "Default")
      (node (ref "D402") (pin "A") (pinfunction "A_A") (pintype "passive"))
      (node (ref "IC401") (pin "1") (pinfunction "RG1_1") (pintype "bidirectional"))
      (node (ref "VR401") (pin "CCW") (pinfunction "A_CCW") (pintype "passive"))
      (node (ref "VR401") (pin "WIP") (pinfunction "S_WIP") (pintype "passive"))
    )
    (net (code "160") (name "Net-(R1-2)") (class "Default")
      (node (ref "D1") (pin "A") (pinfunction "A_A") (pintype "passive"))
      (node (ref "R1") (pin "P$2") (pinfunction "2_P$2") (pintype "passive"))
      (node (ref "R2") (pin "P$1") (pinfunction "1_P$1") (pintype "passive"))
      (node (ref "U1") (pin "2") (pinfunction "-IN_2") (pintype "input"))
    )
    (net (code "161") (name "Net-(R2-2)") (class "Default")
      (node (ref "D2") (pin "C") (pinfunction "C_C") (pintype "passive"))
      (node (ref "R2") (pin "P$2") (pinfunction "2_P$2") (pintype "passive"))
      (node (ref "R3") (pin "P$1") (pinfunction "1_P$1") (pintype "passive"))
    )
    (net (code "162") (name "Net-(R4-2)") (class "Default")
      (node (ref "D3") (pin "A") (pinfunction "A_A") (pintype "passive"))
      (node (ref "R4") (pin "P$2") (pinfunction "2_P$2") (pintype "passive"))
      (node (ref "R5") (pin "P$1") (pinfunction "1_P$1") (pintype "passive"))
      (node (ref "U1") (pin "6") (pinfunction "-IN_6") (pintype "input"))
    )
    (net (code "163") (name "Net-(R5-2)") (class "Default")
      (node (ref "D4") (pin "C") (pinfunction "C_C") (pintype "passive"))
      (node (ref "R5") (pin "P$2") (pinfunction "2_P$2") (pintype "passive"))
      (node (ref "R6") (pin "P$1") (pinfunction "1_P$1") (pintype "passive"))
    )
    (net (code "164") (name "Net-(R101-2)") (class "Default")
      (node (ref "J103") (pin "1") (pinfunction "1_1") (pintype "passive"))
      (node (ref "R101") (pin "P$2") (pinfunction "2_P$2") (pintype "passive"))
      (node (ref "R102") (pin "P$2") (pinfunction "2_P$2") (pintype "passive"))
    )
    (net (code "165") (name "Net-(R107-1)") (class "Default")
      (node (ref "R107") (pin "P$1") (pinfunction "1_P$1") (pintype "passive"))
      (node (ref "R108") (pin "P$2") (pinfunction "2_P$2") (pintype "passive"))
      (node (ref "R109") (pin "P$1") (pinfunction "1_P$1") (pintype "passive"))
    )
    (net (code "166") (name "Net-(R110-1)") (class "Default")
      (node (ref "R110") (pin "P$1") (pinfunction "1_P$1") (pintype "passive"))
      (node (ref "VR101") (pin "CW") (pinfunction "E_CW") (pintype "passive"))
    )
    (net (code "167") (name "Net-(R114-1)") (class "Default")
      (node (ref "R114") (pin "P$1") (pinfunction "1_P$1") (pintype "passive"))
      (node (ref "VR103") (pin "WIP") (pinfunction "S_WIP") (pintype "passive"))
    )
    (net (code "168") (name "Net-(R201-2)") (class "Default")
      (node (ref "J203") (pin "1") (pinfunction "1_1") (pintype "passive"))
      (node (ref "R201") (pin "P$2") (pinfunction "2_P$2") (pintype "passive"))
      (node (ref "R202") (pin "P$2") (pinfunction "2_P$2") (pintype "passive"))
    )
    (net (code "169") (name "Net-(R207-1)") (class "Default")
      (node (ref "R207") (pin "P$1") (pinfunction "1_P$1") (pintype "passive"))
      (node (ref "R208") (pin "P$2") (pinfunction "2_P$2") (pintype "passive"))
      (node (ref "R209") (pin "P$1") (pinfunction "1_P$1") (pintype "passive"))
    )
    (net (code "170") (name "Net-(R210-1)") (class "Default")
      (node (ref "R210") (pin "P$1") (pinfunction "1_P$1") (pintype "passive"))
      (node (ref "VR201") (pin "CW") (pinfunction "E_CW") (pintype "passive"))
    )
    (net (code "171") (name "Net-(R214-1)") (class "Default")
      (node (ref "R214") (pin "P$1") (pinfunction "1_P$1") (pintype "passive"))
      (node (ref "VR203") (pin "WIP") (pinfunction "S_WIP") (pintype "passive"))
    )
    (net (code "172") (name "Net-(R301-2)") (class "Default")
      (node (ref "J303") (pin "1") (pinfunction "1_1") (pintype "passive"))
      (node (ref "R301") (pin "P$2") (pinfunction "2_P$2") (pintype "passive"))
      (node (ref "R302") (pin "P$2") (pinfunction "2_P$2") (pintype "passive"))
    )
    (net (code "173") (name "Net-(R307-1)") (class "Default")
      (node (ref "R307") (pin "P$1") (pinfunction "1_P$1") (pintype "passive"))
      (node (ref "R308") (pin "P$2") (pinfunction "2_P$2") (pintype "passive"))
      (node (ref "R309") (pin "P$1") (pinfunction "1_P$1") (pintype "passive"))
    )
    (net (code "174") (name "Net-(R310-1)") (class "Default")
      (node (ref "R310") (pin "P$1") (pinfunction "1_P$1") (pintype "passive"))
      (node (ref "VR301") (pin "CW") (pinfunction "E_CW") (pintype "passive"))
    )
    (net (code "175") (name "Net-(R314-1)") (class "Default")
      (node (ref "R314") (pin "P$1") (pinfunction "1_P$1") (pintype "passive"))
      (node (ref "VR303") (pin "WIP") (pinfunction "S_WIP") (pintype "passive"))
    )
    (net (code "176") (name "Net-(R401-2)") (class "Default")
      (node (ref "J403") (pin "1") (pinfunction "1_1") (pintype "passive"))
      (node (ref "R401") (pin "P$2") (pinfunction "2_P$2") (pintype "passive"))
      (node (ref "R402") (pin "P$2") (pinfunction "2_P$2") (pintype "passive"))
    )
    (net (code "177") (name "Net-(R407-1)") (class "Default")
      (node (ref "R407") (pin "P$1") (pinfunction "1_P$1") (pintype "passive"))
      (node (ref "R408") (pin "P$2") (pinfunction "2_P$2") (pintype "passive"))
      (node (ref "R409") (pin "P$1") (pinfunction "1_P$1") (pintype "passive"))
    )
    (net (code "178") (name "Net-(R410-1)") (class "Default")
      (node (ref "R410") (pin "P$1") (pinfunction "1_P$1") (pintype "passive"))
      (node (ref "VR401") (pin "CW") (pinfunction "E_CW") (pintype "passive"))
    )
    (net (code "179") (name "Net-(R414-1)") (class "Default")
      (node (ref "R414") (pin "P$1") (pinfunction "1_P$1") (pintype "passive"))
      (node (ref "VR403") (pin "WIP") (pinfunction "S_WIP") (pintype "passive"))
    )
    (net (code "180") (name "Net-(R505-2)") (class "Default")
      (node (ref "R505") (pin "P$2") (pinfunction "2_P$2") (pintype "passive"))
      (node (ref "U501") (pin "3") (pinfunction "+IN_3") (pintype "input"))
    )
    (net (code "181") (name "Net-(R509-1)") (class "Default")
      (node (ref "R509") (pin "P$1") (pinfunction "1_P$1") (pintype "passive"))
      (node (ref "R510") (pin "P$2") (pinfunction "2_P$2") (pintype "passive"))
      (node (ref "U502") (pin "8") (pinfunction "REFADJ_8") (pintype "passive"))
    )
    (net (code "182") (name "Net-(R510-1)") (class "Default")
      (node (ref "R510") (pin "P$1") (pinfunction "1_P$1") (pintype "passive"))
      (node (ref "R511") (pin "P$2") (pinfunction "2_P$2") (pintype "passive"))
      (node (ref "U502") (pin "7") (pinfunction "REFOUT_7") (pintype "output"))
    )
    (net (code "183") (name "Net-(R511-1)") (class "Default")
      (node (ref "R511") (pin "P$1") (pinfunction "1_P$1") (pintype "passive"))
      (node (ref "U502") (pin "6") (pinfunction "RHI_6") (pintype "input"))
    )
    (net (code "184") (name "Net-(R605-2)") (class "Default")
      (node (ref "R605") (pin "P$2") (pinfunction "2_P$2") (pintype "passive"))
      (node (ref "U601") (pin "3") (pinfunction "+IN_3") (pintype "input"))
    )
    (net (code "185") (name "Net-(R609-1)") (class "Default")
      (node (ref "R609") (pin "P$1") (pinfunction "1_P$1") (pintype "passive"))
      (node (ref "R610") (pin "P$2") (pinfunction "2_P$2") (pintype "passive"))
      (node (ref "U602") (pin "8") (pinfunction "REFADJ_8") (pintype "passive"))
    )
    (net (code "186") (name "Net-(R610-1)") (class "Default")
      (node (ref "R610") (pin "P$1") (pinfunction "1_P$1") (pintype "passive"))
      (node (ref "R611") (pin "P$2") (pinfunction "2_P$2") (pintype "passive"))
      (node (ref "U602") (pin "7") (pinfunction "REFOUT_7") (pintype "output"))
    )
    (net (code "187") (name "Net-(R611-1)") (class "Default")
      (node (ref "R611") (pin "P$1") (pinfunction "1_P$1") (pintype "passive"))
      (node (ref "U602") (pin "6") (pinfunction "RHI_6") (pintype "input"))
    )
    (net (code "188") (name "Net-(R701-2)") (class "Default")
      (node (ref "J701") (pin "3") (pinfunction "3_3") (pintype "passive"))
      (node (ref "R701") (pin "P$2") (pinfunction "2_P$2") (pintype "passive"))
    )
    (net (code "189") (name "Net-(R702-2)") (class "Default")
      (node (ref "J701") (pin "1") (pinfunction "1_1") (pintype "passive"))
      (node (ref "R702") (pin "P$2") (pinfunction "2_P$2") (pintype "passive"))
    )
    (net (code "190") (name "Net-(R703-2)") (class "Default")
      (node (ref "D701") (pin "A") (pinfunction "A_A") (pintype "passive"))
      (node (ref "R703") (pin "P$2") (pinfunction "2_P$2") (pintype "passive"))
    )
    (net (code "191") (name "Net-(U1A-OUT)") (class "Default")
      (node (ref "D1") (pin "C") (pinfunction "C_C") (pintype "passive"))
      (node (ref "D2") (pin "A") (pinfunction "A_A") (pintype "passive"))
      (node (ref "U1") (pin "1") (pinfunction "OUT_1") (pintype "output"))
    )
    (net (code "192") (name "Net-(U1B-OUT)") (class "Default")
      (node (ref "D3") (pin "C") (pinfunction "C_C") (pintype "passive"))
      (node (ref "D4") (pin "A") (pinfunction "A_A") (pintype "passive"))
      (node (ref "U1") (pin "7") (pinfunction "OUT_7") (pintype "output"))
    )
    (net (code "193") (name "VCC") (class "Default")
      (node (ref "C112") (pin "P$1") (pinfunction "1_P$1") (pintype "passive"))
      (node (ref "C121") (pin "P$1") (pinfunction "1_P$1") (pintype "passive"))
      (node (ref "C2") (pin "P$1") (pinfunction "1_P$1") (pintype "passive"))
      (node (ref "C212") (pin "P$1") (pinfunction "1_P$1") (pintype "passive"))
      (node (ref "C221") (pin "P$1") (pinfunction "1_P$1") (pintype "passive"))
      (node (ref "C312") (pin "P$1") (pinfunction "1_P$1") (pintype "passive"))
      (node (ref "C321") (pin "P$1") (pinfunction "1_P$1") (pintype "passive"))
      (node (ref "C412") (pin "P$1") (pinfunction "1_P$1") (pintype "passive"))
      (node (ref "C421") (pin "P$1") (pinfunction "1_P$1") (pintype "passive"))
      (node (ref "C503") (pin "P$1") (pinfunction "1_P$1") (pintype "passive"))
      (node (ref "C603") (pin "P$1") (pinfunction "1_P$1") (pintype "passive"))
      (node (ref "C701") (pin "POS") (pinfunction "+_POS") (pintype "passive"))
      (node (ref "D101") (pin "POS") (pinfunction "+_POS") (pintype "bidirectional"))
      (node (ref "D201") (pin "POS") (pinfunction "+_POS") (pintype "bidirectional"))
      (node (ref "D301") (pin "POS") (pinfunction "+_POS") (pintype "bidirectional"))
      (node (ref "D401") (pin "POS") (pinfunction "+_POS") (pintype "bidirectional"))
      (node (ref "D501") (pin "POS") (pinfunction "+_POS") (pintype "bidirectional"))
      (node (ref "D502") (pin "1") (pinfunction "A_1") (pintype "passive"))
      (node (ref "D502") (pin "10") (pinfunction "A9_10") (pintype "passive"))
      (node (ref "D502") (pin "2") (pinfunction "A1_2") (pintype "passive"))
      (node (ref "D502") (pin "3") (pinfunction "A2_3") (pintype "passive"))
      (node (ref "D502") (pin "4") (pinfunction "A3_4") (pintype "passive"))
      (node (ref "D502") (pin "5") (pinfunction "A4_5") (pintype "passive"))
      (node (ref "D502") (pin "6") (pinfunction "A5_6") (pintype "passive"))
      (node (ref "D502") (pin "7") (pinfunction "A6_7") (pintype "passive"))
      (node (ref "D502") (pin "8") (pinfunction "A7_8") (pintype "passive"))
      (node (ref "D502") (pin "9") (pinfunction "A8_9") (pintype "passive"))
      (node (ref "D601") (pin "POS") (pinfunction "+_POS") (pintype "bidirectional"))
      (node (ref "D602") (pin "1") (pinfunction "A_1") (pintype "passive"))
      (node (ref "D602") (pin "10") (pinfunction "A9_10") (pintype "passive"))
      (node (ref "D602") (pin "2") (pinfunction "A1_2") (pintype "passive"))
      (node (ref "D602") (pin "3") (pinfunction "A2_3") (pintype "passive"))
      (node (ref "D602") (pin "4") (pinfunction "A3_4") (pintype "passive"))
      (node (ref "D602") (pin "5") (pinfunction "A4_5") (pintype "passive"))
      (node (ref "D602") (pin "6") (pinfunction "A5_6") (pintype "passive"))
      (node (ref "D602") (pin "7") (pinfunction "A6_7") (pintype "passive"))
      (node (ref "D602") (pin "8") (pinfunction "A7_8") (pintype "passive"))
      (node (ref "D602") (pin "9") (pinfunction "A8_9") (pintype "passive"))
      (node (ref "IC101") (pin "7") (pinfunction "V+_7") (pintype "bidirectional"))
      (node (ref "IC201") (pin "7") (pinfunction "V+_7") (pintype "bidirectional"))
      (node (ref "IC301") (pin "7") (pinfunction "V+_7") (pintype "bidirectional"))
      (node (ref "IC401") (pin "7") (pinfunction "V+_7") (pintype "bidirectional"))
      (node (ref "R701") (pin "P$1") (pinfunction "1_P$1") (pintype "passive"))
      (node (ref "R703") (pin "P$1") (pinfunction "1_P$1") (pintype "passive"))
      (node (ref "U1") (pin "8") (pinfunction "P$V+_8") (pintype "bidirectional"))
      (node (ref "U101") (pin "7") (pinfunction "P$V+_7") (pintype "bidirectional"))
      (node (ref "U201") (pin "7") (pinfunction "P$V+_7") (pintype "bidirectional"))
      (node (ref "U301") (pin "7") (pinfunction "P$V+_7") (pintype "bidirectional"))
      (node (ref "U401") (pin "7") (pinfunction "P$V+_7") (pintype "bidirectional"))
      (node (ref "U501") (pin "7") (pinfunction "P$V+_7") (pintype "bidirectional"))
      (node (ref "U502") (pin "3") (pinfunction "V+_3") (pintype "power_in"))
      (node (ref "U601") (pin "7") (pinfunction "P$V+_7") (pintype "bidirectional"))
      (node (ref "U602") (pin "3") (pinfunction "V+_3") (pintype "power_in"))
    )
    (net (code "194") (name "VNEG") (class "Default")
      (node (ref "C1") (pin "P$2") (pinfunction "2_P$2") (pintype "passive"))
      (node (ref "C113") (pin "P$1") (pinfunction "1_P$1") (pintype "passive"))
      (node (ref "C122") (pin "P$2") (pinfunction "2_P$2") (pintype "passive"))
      (node (ref "C213") (pin "P$1") (pinfunction "1_P$1") (pintype "passive"))
      (node (ref "C222") (pin "P$2") (pinfunction "2_P$2") (pintype "passive"))
      (node (ref "C313") (pin "P$1") (pinfunction "1_P$1") (pintype "passive"))
      (node (ref "C322") (pin "P$2") (pinfunction "2_P$2") (pintype "passive"))
      (node (ref "C413") (pin "P$1") (pinfunction "1_P$1") (pintype "passive"))
      (node (ref "C422") (pin "P$2") (pinfunction "2_P$2") (pintype "passive"))
      (node (ref "C504") (pin "P$2") (pinfunction "2_P$2") (pintype "passive"))
      (node (ref "C604") (pin "P$2") (pinfunction "2_P$2") (pintype "passive"))
      (node (ref "C702") (pin "NEG") (pinfunction "-_NEG") (pintype "passive"))
      (node (ref "D101") (pin "NEG") (pinfunction "-_NEG") (pintype "bidirectional"))
      (node (ref "D201") (pin "NEG") (pinfunction "-_NEG") (pintype "bidirectional"))
      (node (ref "D301") (pin "NEG") (pinfunction "-_NEG") (pintype "bidirectional"))
      (node (ref "D401") (pin "NEG") (pinfunction "-_NEG") (pintype "bidirectional"))
      (node (ref "D501") (pin "NEG") (pinfunction "-_NEG") (pintype "bidirectional"))
      (node (ref "D601") (pin "NEG") (pinfunction "-_NEG") (pintype "bidirectional"))
      (node (ref "IC101") (pin "4") (pinfunction "V-_4") (pintype "bidirectional"))
      (node (ref "IC201") (pin "4") (pinfunction "V-_4") (pintype "bidirectional"))
      (node (ref "IC301") (pin "4") (pinfunction "V-_4") (pintype "bidirectional"))
      (node (ref "IC401") (pin "4") (pinfunction "V-_4") (pintype "bidirectional"))
      (node (ref "R702") (pin "P$1") (pinfunction "1_P$1") (pintype "passive"))
      (node (ref "U1") (pin "4") (pinfunction "P$V-_4") (pintype "bidirectional"))
      (node (ref "U101") (pin "4") (pinfunction "P$V-_4") (pintype "bidirectional"))
      (node (ref "U201") (pin "4") (pinfunction "P$V-_4") (pintype "bidirectional"))
      (node (ref "U301") (pin "4") (pinfunction "P$V-_4") (pintype "bidirectional"))
      (node (ref "U401") (pin "4") (pinfunction "P$V-_4") (pintype "bidirectional"))
      (node (ref "U501") (pin "4") (pinfunction "P$V-_4") (pintype "bidirectional"))
      (node (ref "U601") (pin "4") (pinfunction "P$V-_4") (pintype "bidirectional"))
    )
    (net (code "195") (name "unconnected-(U502-MODE-Pad9)") (class "Default")
      (node (ref "U502") (pin "9") (pinfunction "MODE_9") (pintype "input"))
    )
    (net (code "196") (name "unconnected-(U602-MODE-Pad9)") (class "Default")
      (node (ref "U602") (pin "9") (pinfunction "MODE_9") (pintype "input"))
    )
    (net (code "197") (name "unconnected-(VR104-E-PadCW)") (class "Default")
      (node (ref "VR104") (pin "CW") (pinfunction "E_CW") (pintype "passive"))
    )
    (net (code "198") (name "unconnected-(VR104-S-PadWIP)") (class "Default")
      (node (ref "VR104") (pin "WIP") (pinfunction "S_WIP") (pintype "passive"))
    )
    (net (code "199") (name "unconnected-(VR105-E-PadCW)") (class "Default")
      (node (ref "VR105") (pin "CW") (pinfunction "E_CW") (pintype "passive"))
    )
    (net (code "200") (name "unconnected-(VR105-S-PadWIP)") (class "Default")
      (node (ref "VR105") (pin "WIP") (pinfunction "S_WIP") (pintype "passive"))
    )
    (net (code "201") (name "unconnected-(VR204-E-PadCW)") (class "Default")
      (node (ref "VR204") (pin "CW") (pinfunction "E_CW") (pintype "passive"))
    )
    (net (code "202") (name "unconnected-(VR204-S-PadWIP)") (class "Default")
      (node (ref "VR204") (pin "WIP") (pinfunction "S_WIP") (pintype "passive"))
    )
    (net (code "203") (name "unconnected-(VR205-E-PadCW)") (class "Default")
      (node (ref "VR205") (pin "CW") (pinfunction "E_CW") (pintype "passive"))
    )
    (net (code "204") (name "unconnected-(VR205-S-PadWIP)") (class "Default")
      (node (ref "VR205") (pin "WIP") (pinfunction "S_WIP") (pintype "passive"))
    )
    (net (code "205") (name "unconnected-(VR304-E-PadCW)") (class "Default")
      (node (ref "VR304") (pin "CW") (pinfunction "E_CW") (pintype "passive"))
    )
    (net (code "206") (name "unconnected-(VR304-S-PadWIP)") (class "Default")
      (node (ref "VR304") (pin "WIP") (pinfunction "S_WIP") (pintype "passive"))
    )
    (net (code "207") (name "unconnected-(VR305-E-PadCW)") (class "Default")
      (node (ref "VR305") (pin "CW") (pinfunction "E_CW") (pintype "passive"))
    )
    (net (code "208") (name "unconnected-(VR305-S-PadWIP)") (class "Default")
      (node (ref "VR305") (pin "WIP") (pinfunction "S_WIP") (pintype "passive"))
    )
    (net (code "209") (name "unconnected-(VR404-E-PadCW)") (class "Default")
      (node (ref "VR404") (pin "CW") (pinfunction "E_CW") (pintype "passive"))
    )
    (net (code "210") (name "unconnected-(VR404-S-PadWIP)") (class "Default")
      (node (ref "VR404") (pin "WIP") (pinfunction "S_WIP") (pintype "passive"))
    )
    (net (code "211") (name "unconnected-(VR405-E-PadCW)") (class "Default")
      (node (ref "VR405") (pin "CW") (pinfunction "E_CW") (pintype "passive"))
    )
    (net (code "212") (name "unconnected-(VR405-S-PadWIP)") (class "Default")
      (node (ref "VR405") (pin "WIP") (pinfunction "S_WIP") (pintype "passive"))
    )
  )
)
